# homeboard28.net
KiCad netlist of a schematic drawn in EAGLE
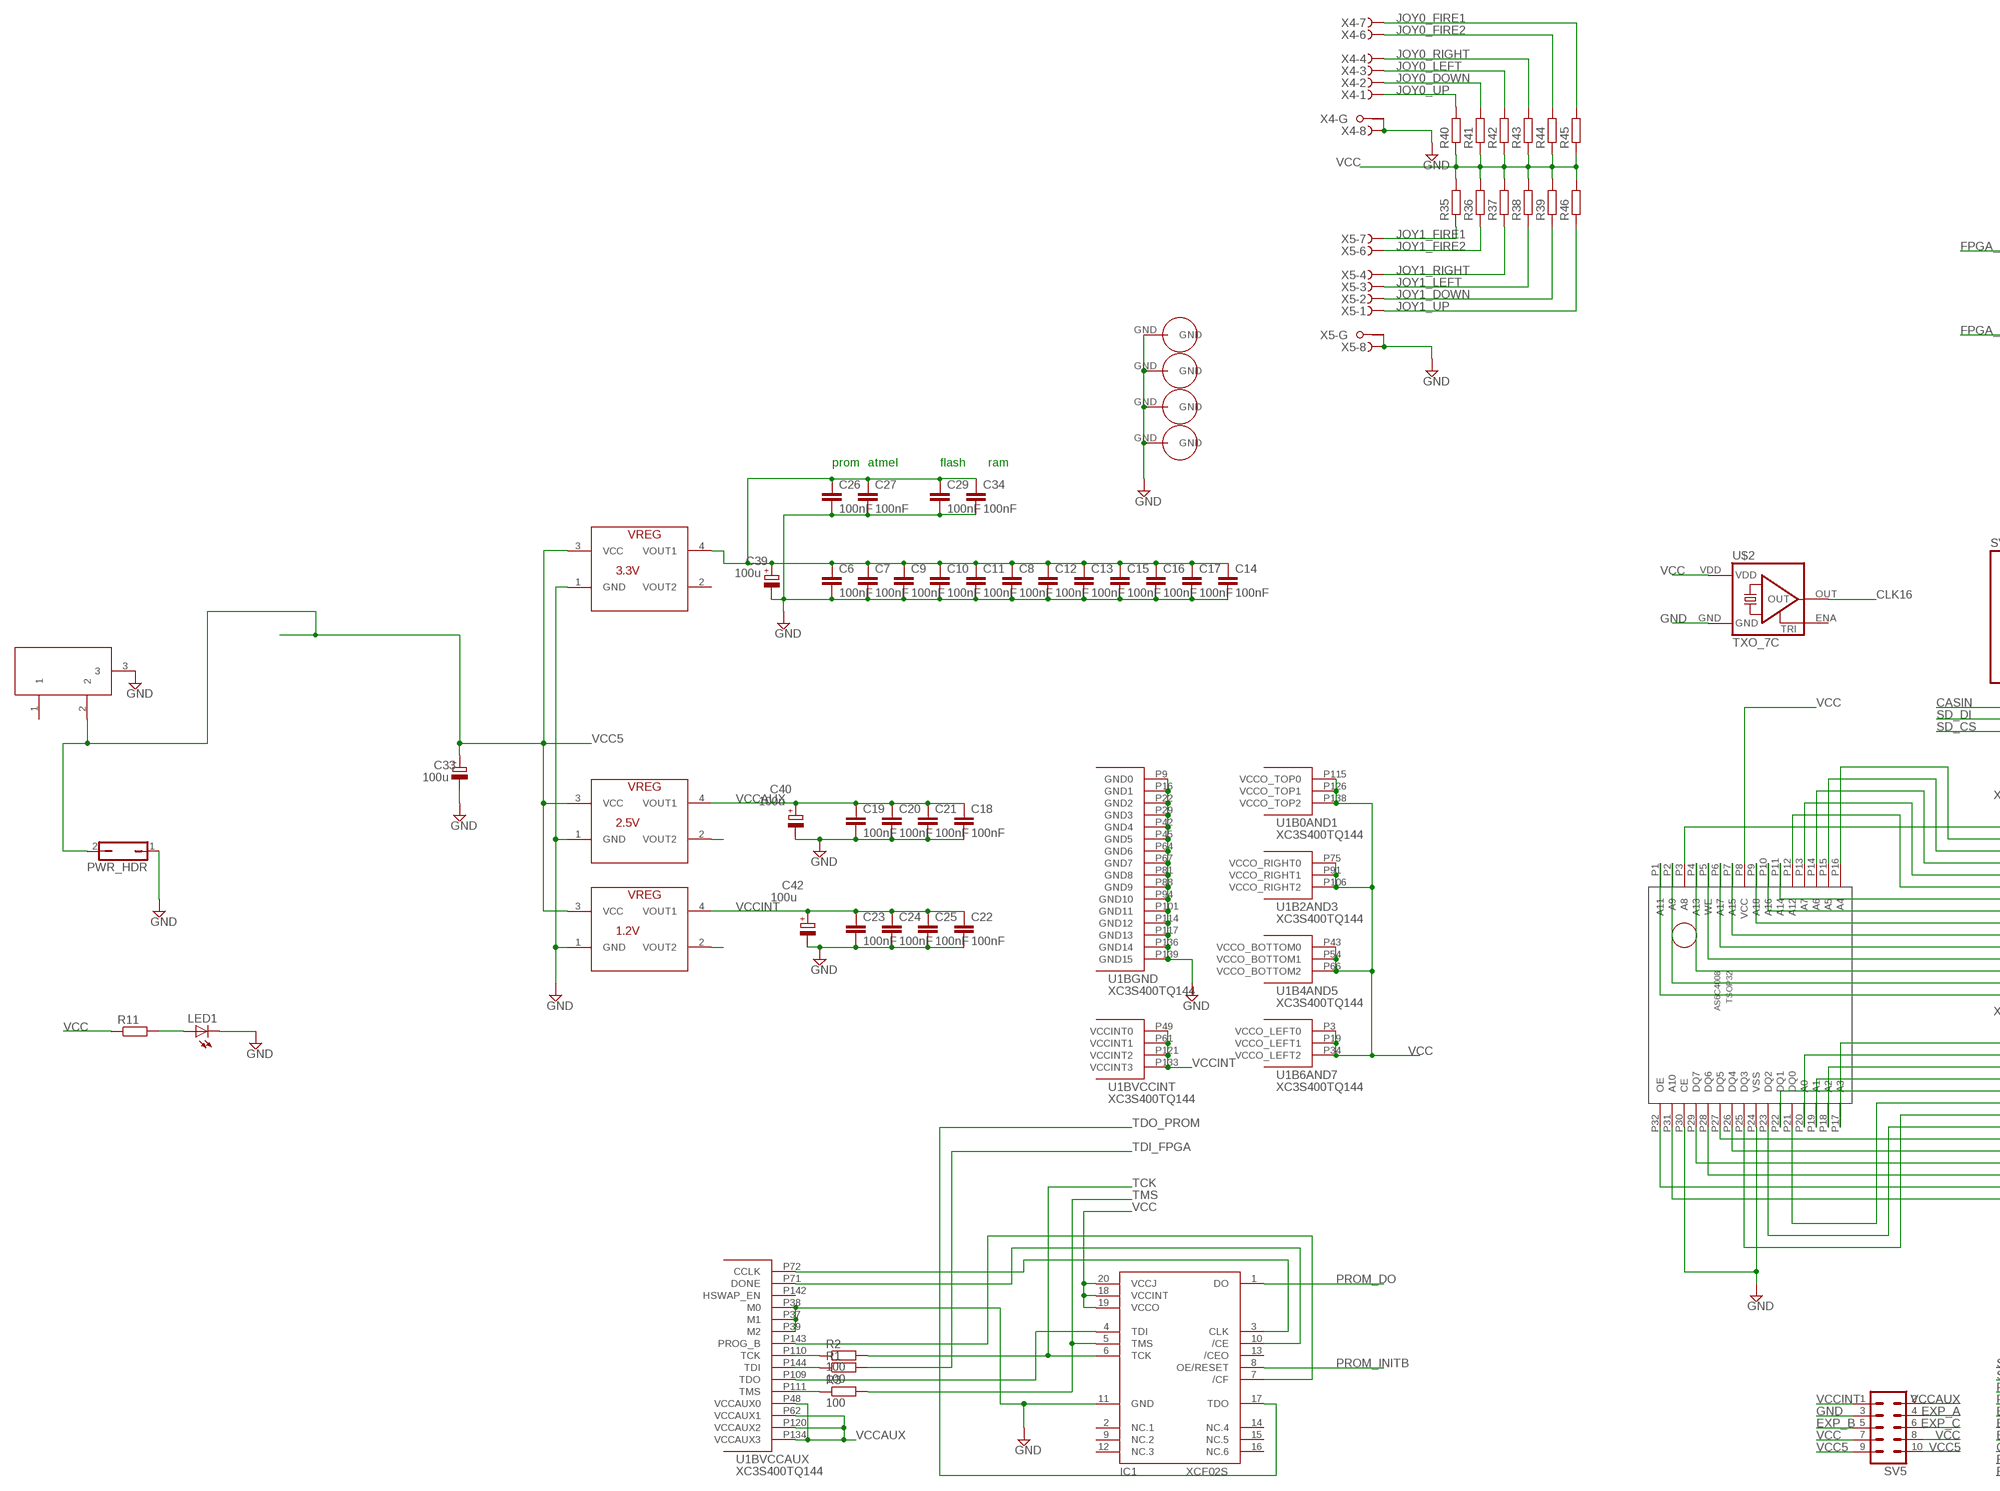
[diagram p0: schematic, sheet 1, part 1 of 3]
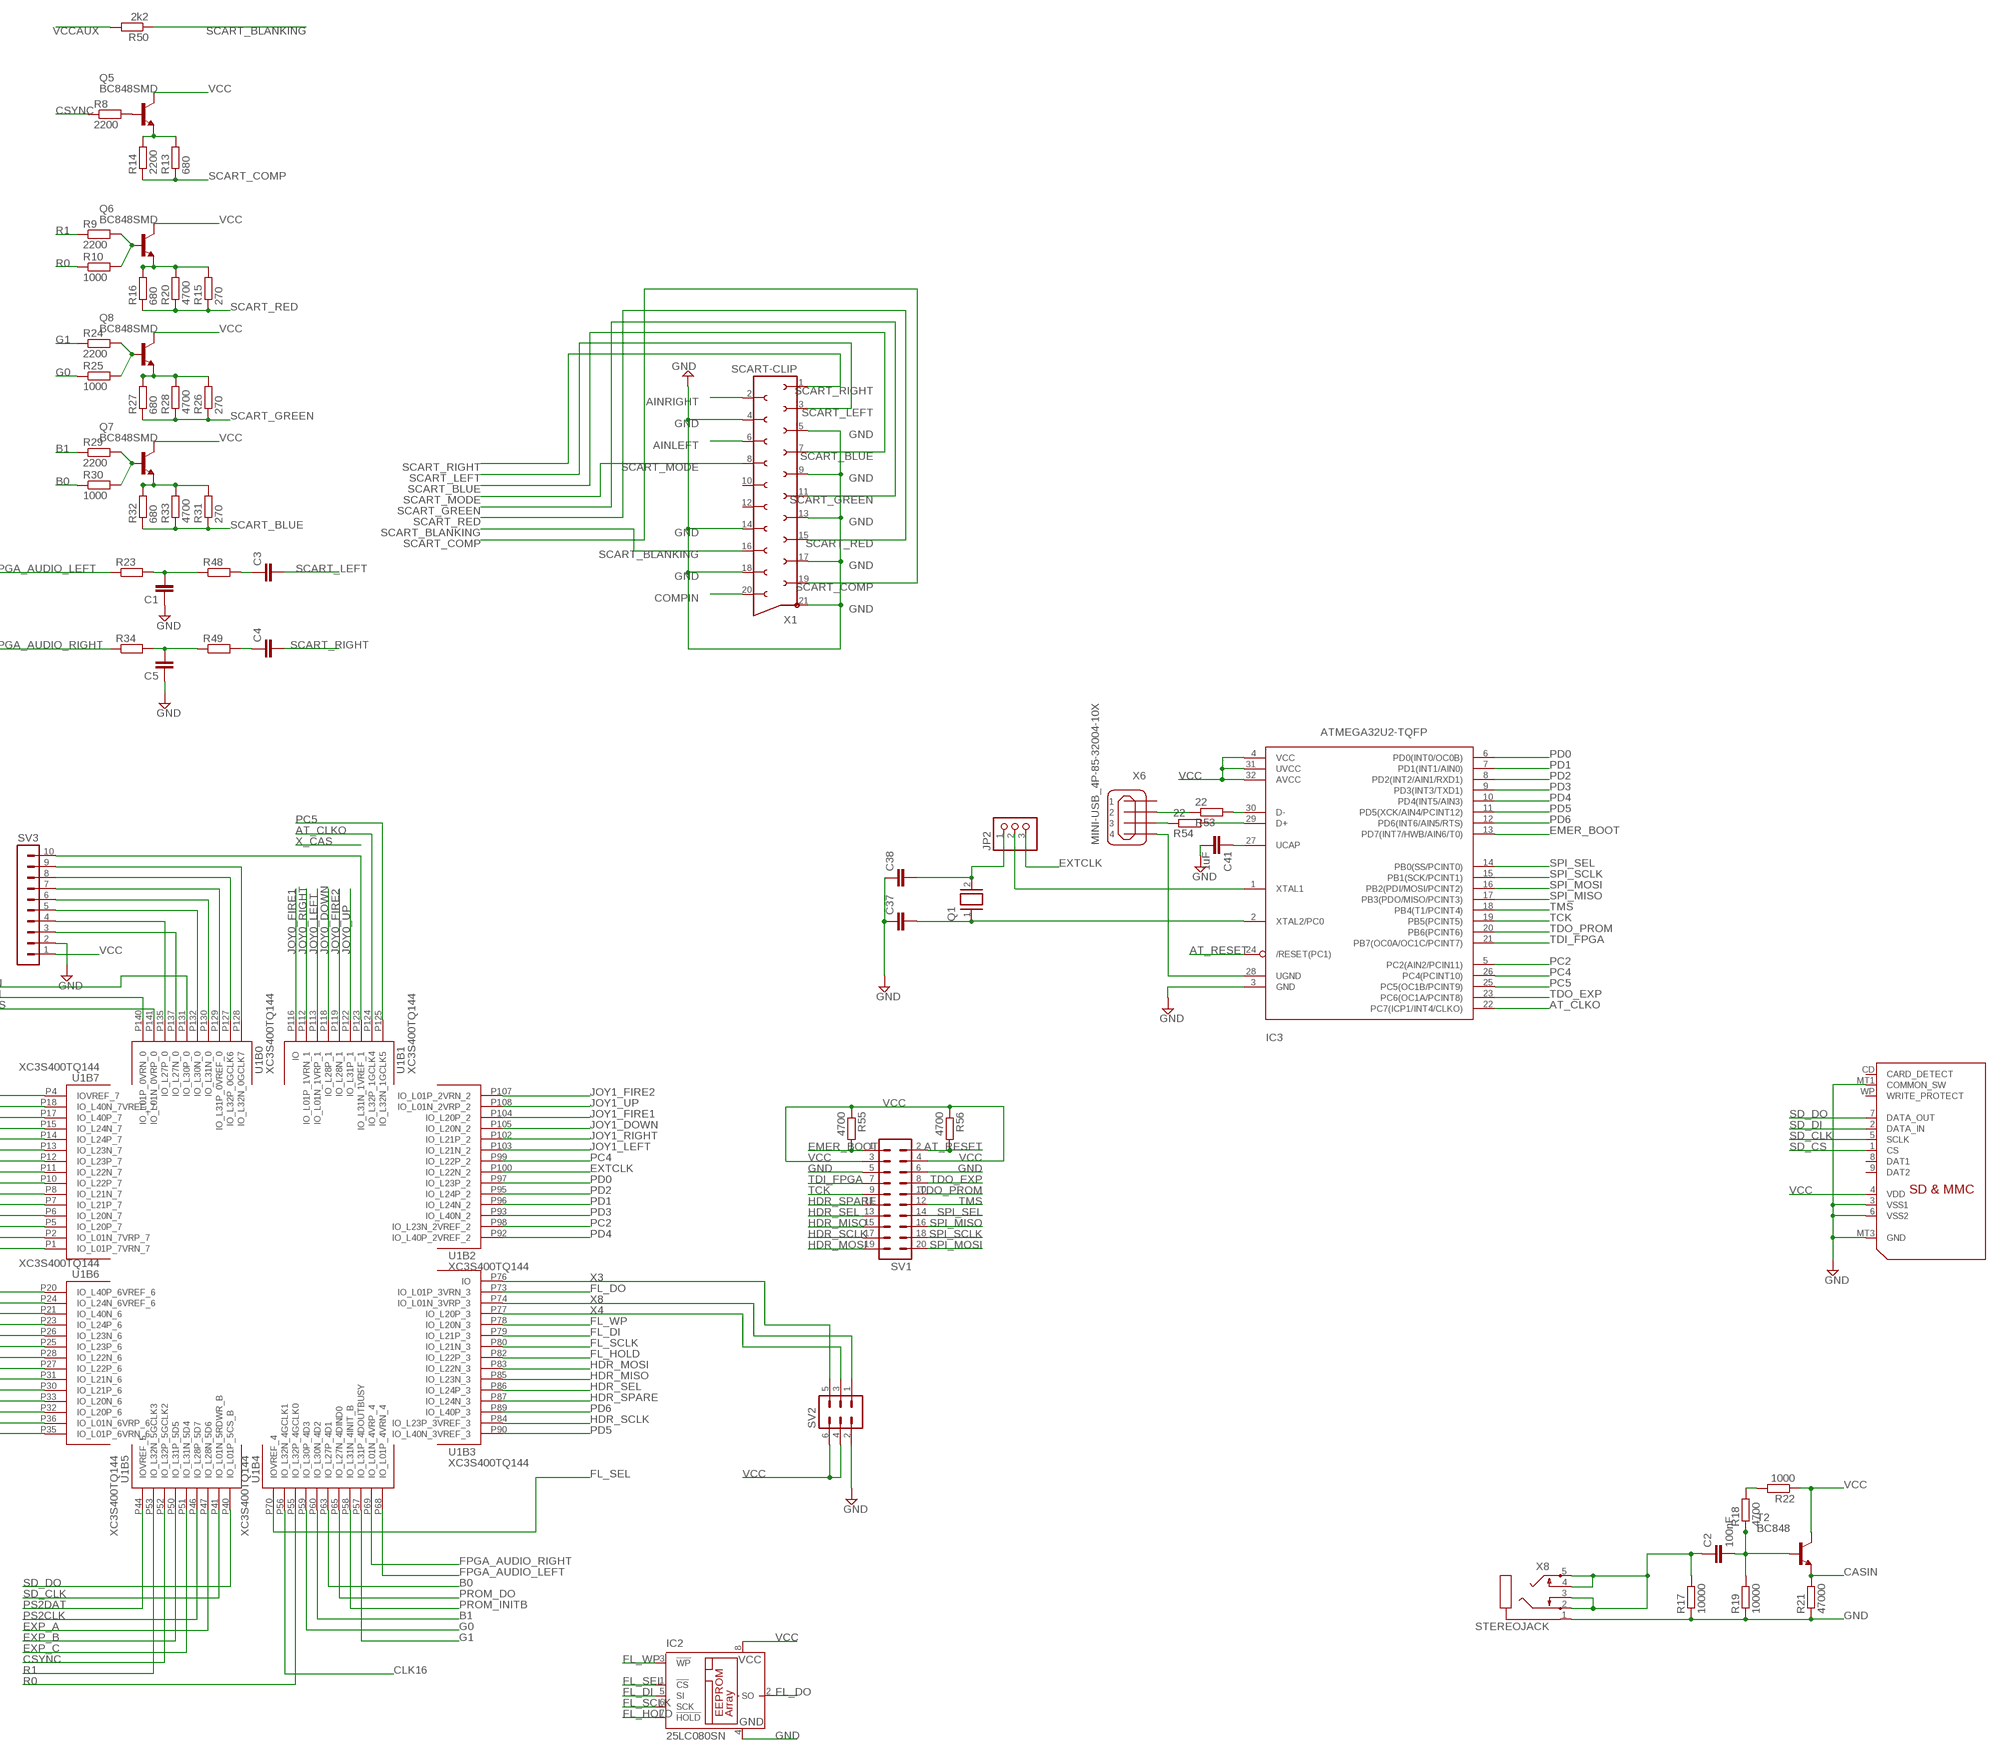
[diagram p1: schematic, sheet 1, part 2 of 3]
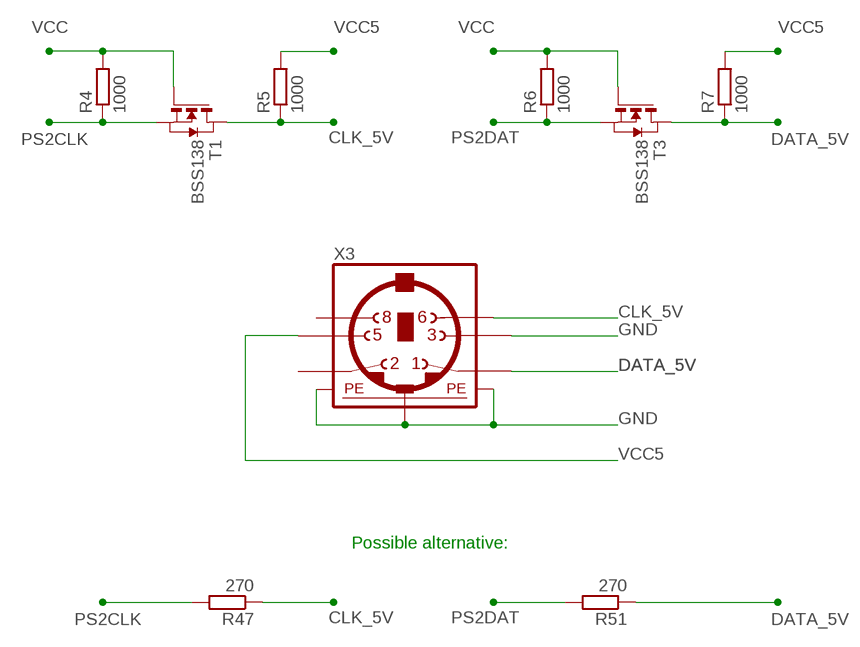
[diagram p2: schematic, sheet 1, part 3 of 3]

(export (version "E")
  (design (tool "Eeschema 10.0.6"))
  (components
    (comp (ref "C1")
      (value "C-EUC0603")
      (footprint "eagle-import:C0603")
      (libsource (lib "eagle-import") (part "resistor_C-EUC0603"))
    )
    (comp (ref "C2")
      (value "100nF")
      (footprint "eagle-import:C0603")
      (libsource (lib "eagle-import") (part "resistor_C-EUC0603"))
    )
    (comp (ref "C3")
      (value "C-EUC0603")
      (footprint "eagle-import:C0603")
      (libsource (lib "eagle-import") (part "resistor_C-EUC0603"))
    )
    (comp (ref "C4")
      (value "C-EUC0603")
      (footprint "eagle-import:C0603")
      (libsource (lib "eagle-import") (part "resistor_C-EUC0603"))
    )
    (comp (ref "C5")
      (value "C-EUC0603")
      (footprint "eagle-import:C0603")
      (libsource (lib "eagle-import") (part "resistor_C-EUC0603"))
    )
    (comp (ref "C6")
      (value "100nF")
      (footprint "eagle-import:C0603")
      (libsource (lib "eagle-import") (part "C-EUC0603"))
    )
    (comp (ref "C7")
      (value "100nF")
      (footprint "eagle-import:C0603")
      (libsource (lib "eagle-import") (part "C-EUC0603"))
    )
    (comp (ref "C8")
      (value "100nF")
      (footprint "eagle-import:C0603")
      (libsource (lib "eagle-import") (part "C-EUC0603"))
    )
    (comp (ref "C9")
      (value "100nF")
      (footprint "eagle-import:C0603")
      (libsource (lib "eagle-import") (part "C-EUC0603"))
    )
    (comp (ref "C10")
      (value "100nF")
      (footprint "eagle-import:C0603")
      (libsource (lib "eagle-import") (part "C-EUC0603"))
    )
    (comp (ref "C11")
      (value "100nF")
      (footprint "eagle-import:C0603")
      (libsource (lib "eagle-import") (part "C-EUC0603"))
    )
    (comp (ref "C12")
      (value "100nF")
      (footprint "eagle-import:C0603")
      (libsource (lib "eagle-import") (part "C-EUC0603"))
    )
    (comp (ref "C13")
      (value "100nF")
      (footprint "eagle-import:C0603")
      (libsource (lib "eagle-import") (part "C-EUC0603"))
    )
    (comp (ref "C14")
      (value "100nF")
      (footprint "eagle-import:C0603")
      (libsource (lib "eagle-import") (part "C-EUC0603"))
    )
    (comp (ref "C15")
      (value "100nF")
      (footprint "eagle-import:C0603")
      (libsource (lib "eagle-import") (part "C-EUC0603"))
    )
    (comp (ref "C16")
      (value "100nF")
      (footprint "eagle-import:C0603")
      (libsource (lib "eagle-import") (part "C-EUC0603"))
    )
    (comp (ref "C17")
      (value "100nF")
      (footprint "eagle-import:C0603")
      (libsource (lib "eagle-import") (part "C-EUC0603"))
    )
    (comp (ref "C18")
      (value "100nF")
      (footprint "eagle-import:C0603")
      (libsource (lib "eagle-import") (part "C-EUC0603"))
    )
    (comp (ref "C19")
      (value "100nF")
      (footprint "eagle-import:C0603")
      (libsource (lib "eagle-import") (part "C-EUC0603"))
    )
    (comp (ref "C20")
      (value "100nF")
      (footprint "eagle-import:C0603")
      (libsource (lib "eagle-import") (part "C-EUC0603"))
    )
    (comp (ref "C21")
      (value "100nF")
      (footprint "eagle-import:C0603")
      (libsource (lib "eagle-import") (part "C-EUC0603"))
    )
    (comp (ref "C22")
      (value "100nF")
      (footprint "eagle-import:C0603")
      (libsource (lib "eagle-import") (part "C-EUC0603"))
    )
    (comp (ref "C23")
      (value "100nF")
      (footprint "eagle-import:C0603")
      (libsource (lib "eagle-import") (part "C-EUC0603"))
    )
    (comp (ref "C24")
      (value "100nF")
      (footprint "eagle-import:C0603")
      (libsource (lib "eagle-import") (part "C-EUC0603"))
    )
    (comp (ref "C25")
      (value "100nF")
      (footprint "eagle-import:C0603")
      (libsource (lib "eagle-import") (part "C-EUC0603"))
    )
    (comp (ref "C26")
      (value "100nF")
      (footprint "eagle-import:C0603")
      (libsource (lib "eagle-import") (part "C-EUC0603"))
    )
    (comp (ref "C27")
      (value "100nF")
      (footprint "eagle-import:C0603")
      (libsource (lib "eagle-import") (part "C-EUC0603"))
    )
    (comp (ref "C29")
      (value "100nF")
      (footprint "eagle-import:C0603")
      (libsource (lib "eagle-import") (part "C-EUC0603"))
    )
    (comp (ref "C33")
      (value "100u")
      (footprint "eagle-import:PANASONIC_D")
      (libsource (lib "eagle-import") (part "CPOL-EUD"))
    )
    (comp (ref "C34")
      (value "100nF")
      (footprint "eagle-import:C0603")
      (libsource (lib "eagle-import") (part "C-EUC0603"))
    )
    (comp (ref "C37")
      (value "C-EUC0805")
      (footprint "eagle-import:C0805")
      (libsource (lib "eagle-import") (part "C-EUC0805"))
    )
    (comp (ref "C38")
      (value "C-EUC0805")
      (footprint "eagle-import:C0805")
      (libsource (lib "eagle-import") (part "C-EUC0805"))
    )
    (comp (ref "C39")
      (value "100u")
      (footprint "eagle-import:PANASONIC_D")
      (libsource (lib "eagle-import") (part "CPOL-EUD"))
    )
    (comp (ref "C40")
      (value "100u")
      (footprint "eagle-import:PANASONIC_D")
      (libsource (lib "eagle-import") (part "CPOL-EUD"))
    )
    (comp (ref "C41")
      (value "1uF")
      (footprint "eagle-import:C0805")
      (libsource (lib "eagle-import") (part "C-EUC0805"))
    )
    (comp (ref "C42")
      (value "100u")
      (footprint "eagle-import:PANASONIC_D")
      (libsource (lib "eagle-import") (part "CPOL-EUD"))
    )
    (comp (ref "IC1")
      (value "XCF02S")
      (footprint "eagle-import:VO20")
      (libsource (lib "eagle-import") (part "XCF02S"))
    )
    (comp (ref "IC2")
      (value "25LC080SN")
      (footprint "eagle-import:SO-08")
      (fields (field (name "MF") "MICROCHIP") (field (name "MPN") "25LC080/SN"))
      (libsource (lib "eagle-import") (part "25SNLC080"))
    )
    (comp (ref "IC3")
      (value "ATMEGA32U2-TQFP")
      (footprint "eagle-import:TQFP32-08")
      (libsource (lib "eagle-import") (part "ATMEGA32U2-TQFP"))
    )
    (comp (ref "JP2")
      (value "PINHD-1X3")
      (footprint "eagle-import:1X03")
      (libsource (lib "eagle-import") (part "PINHD-1X3"))
    )
    (comp (ref "LED1")
      (value "LEDCHIPLED_0805")
      (footprint "eagle-import:CHIPLED_0805")
      (libsource (lib "eagle-import") (part "LEDCHIPLED_0805"))
    )
    (comp (ref "PWR_HDR")
      (value "JP1Q")
      (footprint "eagle-import:JP1")
      (libsource (lib "eagle-import") (part "JP1Q"))
    )
    (comp (ref "Q1")
      (value "XTAL/S")
      (footprint "eagle-import:QS")
      (libsource (lib "eagle-import") (part "XTAL/S"))
    )
    (comp (ref "Q5")
      (value "BC848SMD")
      (footprint "eagle-import:SOT23")
      (libsource (lib "eagle-import") (part "BC848SMD"))
    )
    (comp (ref "Q6")
      (value "BC848SMD")
      (footprint "eagle-import:SOT23")
      (libsource (lib "eagle-import") (part "BC848SMD"))
    )
    (comp (ref "Q7")
      (value "BC848SMD")
      (footprint "eagle-import:SOT23")
      (libsource (lib "eagle-import") (part "BC848SMD"))
    )
    (comp (ref "Q8")
      (value "BC848SMD")
      (footprint "eagle-import:SOT23")
      (libsource (lib "eagle-import") (part "BC848SMD"))
    )
    (comp (ref "R1")
      (value "100")
      (footprint "eagle-import:R0805")
      (libsource (lib "eagle-import") (part "R-EU_R0805"))
    )
    (comp (ref "R2")
      (value "100")
      (footprint "eagle-import:R0805")
      (libsource (lib "eagle-import") (part "R-EU_R0805"))
    )
    (comp (ref "R3")
      (value "100")
      (footprint "eagle-import:R0805")
      (libsource (lib "eagle-import") (part "R-EU_R0805"))
    )
    (comp (ref "R4")
      (value "1000")
      (footprint "eagle-import:R0805")
      (libsource (lib "eagle-import") (part "R-EU_R0805"))
    )
    (comp (ref "R5")
      (value "1000")
      (footprint "eagle-import:R0805")
      (libsource (lib "eagle-import") (part "R-EU_R0805"))
    )
    (comp (ref "R6")
      (value "1000")
      (footprint "eagle-import:R0805")
      (libsource (lib "eagle-import") (part "R-EU_R0805"))
    )
    (comp (ref "R7")
      (value "1000")
      (footprint "eagle-import:R0805")
      (libsource (lib "eagle-import") (part "R-EU_R0805"))
    )
    (comp (ref "R8")
      (value "2200")
      (footprint "eagle-import:R0805")
      (libsource (lib "eagle-import") (part "R-EU_R0805"))
    )
    (comp (ref "R9")
      (value "2200")
      (footprint "eagle-import:R0805")
      (libsource (lib "eagle-import") (part "R-EU_R0805"))
    )
    (comp (ref "R10")
      (value "1000")
      (footprint "eagle-import:R0805")
      (libsource (lib "eagle-import") (part "R-EU_R0805"))
    )
    (comp (ref "R11")
      (value "R-EU_M0805")
      (footprint "eagle-import:M0805")
      (libsource (lib "eagle-import") (part "resistor_R-EU_M0805"))
    )
    (comp (ref "R13")
      (value "680")
      (footprint "eagle-import:R0805")
      (libsource (lib "eagle-import") (part "R-EU_R0805"))
    )
    (comp (ref "R14")
      (value "2200")
      (footprint "eagle-import:R0805")
      (libsource (lib "eagle-import") (part "R-EU_R0805"))
    )
    (comp (ref "R15")
      (value "270")
      (footprint "eagle-import:R0805")
      (libsource (lib "eagle-import") (part "R-EU_R0805"))
    )
    (comp (ref "R16")
      (value "680")
      (footprint "eagle-import:R0805")
      (libsource (lib "eagle-import") (part "R-EU_R0805"))
    )
    (comp (ref "R17")
      (value "10000")
      (footprint "eagle-import:R0805")
      (libsource (lib "eagle-import") (part "R-EU_R0805"))
    )
    (comp (ref "R18")
      (value "4700")
      (footprint "eagle-import:R0805")
      (libsource (lib "eagle-import") (part "R-EU_R0805"))
    )
    (comp (ref "R19")
      (value "10000")
      (footprint "eagle-import:R0805")
      (libsource (lib "eagle-import") (part "R-EU_R0805"))
    )
    (comp (ref "R20")
      (value "4700")
      (footprint "eagle-import:R0805")
      (libsource (lib "eagle-import") (part "R-EU_R0805"))
    )
    (comp (ref "R21")
      (value "47000")
      (footprint "eagle-import:R0805")
      (libsource (lib "eagle-import") (part "R-EU_R0805"))
    )
    (comp (ref "R22")
      (value "1000")
      (footprint "eagle-import:R0805")
      (libsource (lib "eagle-import") (part "R-EU_R0805"))
    )
    (comp (ref "R23")
      (value "R-EU_M0805")
      (footprint "eagle-import:M0805")
      (libsource (lib "eagle-import") (part "resistor_R-EU_M0805"))
    )
    (comp (ref "R24")
      (value "2200")
      (footprint "eagle-import:R0805")
      (libsource (lib "eagle-import") (part "R-EU_R0805"))
    )
    (comp (ref "R25")
      (value "1000")
      (footprint "eagle-import:R0805")
      (libsource (lib "eagle-import") (part "R-EU_R0805"))
    )
    (comp (ref "R26")
      (value "270")
      (footprint "eagle-import:R0805")
      (libsource (lib "eagle-import") (part "R-EU_R0805"))
    )
    (comp (ref "R27")
      (value "680")
      (footprint "eagle-import:R0805")
      (libsource (lib "eagle-import") (part "R-EU_R0805"))
    )
    (comp (ref "R28")
      (value "4700")
      (footprint "eagle-import:R0805")
      (libsource (lib "eagle-import") (part "R-EU_R0805"))
    )
    (comp (ref "R29")
      (value "2200")
      (footprint "eagle-import:R0805")
      (libsource (lib "eagle-import") (part "R-EU_R0805"))
    )
    (comp (ref "R30")
      (value "1000")
      (footprint "eagle-import:R0805")
      (libsource (lib "eagle-import") (part "R-EU_R0805"))
    )
    (comp (ref "R31")
      (value "270")
      (footprint "eagle-import:R0805")
      (libsource (lib "eagle-import") (part "R-EU_R0805"))
    )
    (comp (ref "R32")
      (value "680")
      (footprint "eagle-import:R0805")
      (libsource (lib "eagle-import") (part "R-EU_R0805"))
    )
    (comp (ref "R33")
      (value "4700")
      (footprint "eagle-import:R0805")
      (libsource (lib "eagle-import") (part "R-EU_R0805"))
    )
    (comp (ref "R34")
      (value "R-EU_M0805")
      (footprint "eagle-import:M0805")
      (libsource (lib "eagle-import") (part "resistor_R-EU_M0805"))
    )
    (comp (ref "R35")
      (value "R-EU_M0805")
      (footprint "eagle-import:M0805")
      (libsource (lib "eagle-import") (part "resistor_R-EU_M0805"))
    )
    (comp (ref "R36")
      (value "R-EU_M0805")
      (footprint "eagle-import:M0805")
      (libsource (lib "eagle-import") (part "resistor_R-EU_M0805"))
    )
    (comp (ref "R37")
      (value "R-EU_M0805")
      (footprint "eagle-import:M0805")
      (libsource (lib "eagle-import") (part "resistor_R-EU_M0805"))
    )
    (comp (ref "R38")
      (value "R-EU_M0805")
      (footprint "eagle-import:M0805")
      (libsource (lib "eagle-import") (part "resistor_R-EU_M0805"))
    )
    (comp (ref "R39")
      (value "R-EU_M0805")
      (footprint "eagle-import:M0805")
      (libsource (lib "eagle-import") (part "resistor_R-EU_M0805"))
    )
    (comp (ref "R40")
      (value "R-EU_M0805")
      (footprint "eagle-import:M0805")
      (libsource (lib "eagle-import") (part "resistor_R-EU_M0805"))
    )
    (comp (ref "R41")
      (value "R-EU_M0805")
      (footprint "eagle-import:M0805")
      (libsource (lib "eagle-import") (part "resistor_R-EU_M0805"))
    )
    (comp (ref "R42")
      (value "R-EU_M0805")
      (footprint "eagle-import:M0805")
      (libsource (lib "eagle-import") (part "resistor_R-EU_M0805"))
    )
    (comp (ref "R43")
      (value "R-EU_M0805")
      (footprint "eagle-import:M0805")
      (libsource (lib "eagle-import") (part "resistor_R-EU_M0805"))
    )
    (comp (ref "R44")
      (value "R-EU_M0805")
      (footprint "eagle-import:M0805")
      (libsource (lib "eagle-import") (part "resistor_R-EU_M0805"))
    )
    (comp (ref "R45")
      (value "R-EU_M0805")
      (footprint "eagle-import:M0805")
      (libsource (lib "eagle-import") (part "resistor_R-EU_M0805"))
    )
    (comp (ref "R46")
      (value "R-EU_M0805")
      (footprint "eagle-import:M0805")
      (libsource (lib "eagle-import") (part "resistor_R-EU_M0805"))
    )
    (comp (ref "R47")
      (value "270")
      (footprint "eagle-import:R0805")
      (libsource (lib "eagle-import") (part "R-EU_R0805"))
    )
    (comp (ref "R48")
      (value "R-EU_M0805")
      (footprint "eagle-import:M0805")
      (libsource (lib "eagle-import") (part "resistor_R-EU_M0805"))
    )
    (comp (ref "R49")
      (value "R-EU_M0805")
      (footprint "eagle-import:M0805")
      (libsource (lib "eagle-import") (part "resistor_R-EU_M0805"))
    )
    (comp (ref "R50")
      (value "2k2")
      (footprint "eagle-import:M0805")
      (libsource (lib "eagle-import") (part "resistor_R-EU_M0805"))
    )
    (comp (ref "R51")
      (value "270")
      (footprint "eagle-import:R0805")
      (libsource (lib "eagle-import") (part "R-EU_R0805"))
    )
    (comp (ref "R53")
      (value "22")
      (footprint "eagle-import:R0805")
      (libsource (lib "eagle-import") (part "R-EU_R0805"))
    )
    (comp (ref "R54")
      (value "22")
      (footprint "eagle-import:R0805")
      (libsource (lib "eagle-import") (part "R-EU_R0805"))
    )
    (comp (ref "R55")
      (value "4700")
      (footprint "eagle-import:R0805")
      (libsource (lib "eagle-import") (part "R-EU_R0805"))
    )
    (comp (ref "R56")
      (value "4700")
      (footprint "eagle-import:R0805")
      (libsource (lib "eagle-import") (part "R-EU_R0805"))
    )
    (comp (ref "REG1.2")
      (value "1.2V")
      (footprint "eagle-import:SOT223")
      (libsource (lib "eagle-import") (part "NX1117"))
    )
    (comp (ref "REG2.5")
      (value "2.5V")
      (footprint "eagle-import:SOT223")
      (libsource (lib "eagle-import") (part "NX1117"))
    )
    (comp (ref "SV1")
      (value "MA10-2")
      (footprint "eagle-import:MA10-2")
      (fields (field (name "OC_FARNELL") "unknown") (field (name "OC_NEWARK") "unknown"))
      (libsource (lib "eagle-import") (part "MA10-2"))
    )
    (comp (ref "SV2")
      (value "MA03-2")
      (footprint "eagle-import:MA03-2")
      (libsource (lib "eagle-import") (part "MA03-2"))
    )
    (comp (ref "SV3")
      (value "MA10-1")
      (footprint "eagle-import:MA10-1")
      (libsource (lib "eagle-import") (part "MA10-1"))
    )
    (comp (ref "SV5")
      (value "MA05-2")
      (footprint "eagle-import:MA05-2")
      (libsource (lib "eagle-import") (part "MA05-2"))
    )
    (comp (ref "T1")
      (value "BSS138")
      (footprint "eagle-import:SOT-23")
      (libsource (lib "eagle-import") (part "NMOSSOT23"))
    )
    (comp (ref "T2")
      (value "BC848")
      (footprint "eagle-import:SOT23")
      (libsource (lib "eagle-import") (part "BC848"))
    )
    (comp (ref "T3")
      (value "BSS138")
      (footprint "eagle-import:SOT-23")
      (libsource (lib "eagle-import") (part "NMOSSOT23"))
    )
    (comp (ref "U$1")
      (value "GNDHOLE")
      (footprint "eagle-import:GNDHOLE")
      (libsource (lib "eagle-import") (part "GNDHOLE"))
    )
    (comp (ref "U$2")
      (value "TXO_7C")
      (footprint "eagle-import:OSC_7C")
      (libsource (lib "eagle-import") (part "TXO_7C"))
    )
    (comp (ref "U$3")
      (value "SDMMCNOHOLE")
      (footprint "eagle-import:SDCARD-NOHOLE")
      (libsource (lib "eagle-import") (part "SDMMCNOHOLE"))
    )
    (comp (ref "U$4")
      (value "3.3V")
      (footprint "eagle-import:SOT223")
      (libsource (lib "eagle-import") (part "NX1117"))
    )
    (comp (ref "U$6")
      (value "AS6C4008")
      (footprint "eagle-import:TSOP32")
      (libsource (lib "eagle-import") (part "AS6C4008"))
    )
    (comp (ref "U$7")
      (value "GNDHOLE")
      (footprint "eagle-import:GNDHOLE")
      (libsource (lib "eagle-import") (part "GNDHOLE"))
    )
    (comp (ref "U$8")
      (value "GNDHOLE")
      (footprint "eagle-import:GNDHOLE")
      (libsource (lib "eagle-import") (part "GNDHOLE"))
    )
    (comp (ref "U$9")
      (value "GNDHOLE")
      (footprint "eagle-import:GNDHOLE")
      (libsource (lib "eagle-import") (part "GNDHOLE"))
    )
    (comp (ref "U1")
      (value "XC3S400TQ144")
      (footprint "eagle-import:TQ144")
      (libsource (lib "eagle-import") (part "XC3S400TQ144"))
    )
    (comp (ref "X1")
      (value "SCART-CLIP")
      (footprint "eagle-import:SCART-CLIP")
      (libsource (lib "eagle-import") (part "SCART-CLIP"))
    )
    (comp (ref "X3")
      (value "MINI_DIN_6")
      (footprint "eagle-import:M_DIN6")
      (libsource (lib "eagle-import") (part "MINI_DIN_6"))
    )
    (comp (ref "X4")
      (value "F09HPS")
      (footprint "eagle-import:F09HP")
      (libsource (lib "eagle-import") (part "F09HPS"))
    )
    (comp (ref "X5")
      (value "F09HPS")
      (footprint "eagle-import:F09HP")
      (libsource (lib "eagle-import") (part "F09HPS"))
    )
    (comp (ref "X6")
      (value "MINI-USB_4P-85-32004-10X")
      (footprint "eagle-import:85-32004-10X")
      (libsource (lib "eagle-import") (part "MINI-USB_4P-85-32004-10X"))
    )
    (comp (ref "X7")
      (value "DC21MMX")
      (footprint "eagle-import:DC-21MM")
      (libsource (lib "eagle-import") (part "DC21MMX"))
    )
    (comp (ref "X8")
      (value "STEREOJACK")
      (footprint "eagle-import:20-0137")
      (libsource (lib "eagle-import") (part "STEREOJACK"))
    )
  )
  (nets
    (net (code "1") (name "/1") (class "Default")
      (node (ref "X7") (pin "1") (pinfunction "1_1") (pintype "power_in"))
    )
    (net (code "2") (name "/AINLEFT") (class "Default")
      (node (ref "X1") (pin "6") (pinfunction "6_6") (pintype "passive"))
    )
    (net (code "3") (name "/AINRIGHT") (class "Default")
      (node (ref "X1") (pin "2") (pinfunction "2_2") (pintype "passive"))
    )
    (net (code "4") (name "/AT_CLKO") (class "Default")
      (node (ref "IC3") (pin "22") (pinfunction "PC7(ICP1/INT4/CLKO)_22") (pintype "bidirectional"))
      (node (ref "U1") (pin "P124") (pinfunction "IO_L32P_1GCLK4_P124") (pintype "bidirectional"))
    )
    (net (code "5") (name "/AT_RESET") (class "Default")
      (node (ref "IC3") (pin "24") (pinfunction "/RESET(PC1)_24") (pintype "bidirectional"))
      (node (ref "R56") (pin "2") (pinfunction "2_2") (pintype "passive"))
      (node (ref "SV1") (pin "2") (pinfunction "2_2") (pintype "passive"))
    )
    (net (code "6") (name "/B0") (class "Default")
      (node (ref "R30") (pin "1") (pinfunction "1_1") (pintype "passive"))
      (node (ref "U1") (pin "P63") (pinfunction "IO_L27P_4D1_P63") (pintype "bidirectional"))
    )
    (net (code "7") (name "/B1") (class "Default")
      (node (ref "R29") (pin "1") (pinfunction "1_1") (pintype "passive"))
      (node (ref "U1") (pin "P60") (pinfunction "IO_L30N_4D2_P60") (pintype "bidirectional"))
    )
    (net (code "8") (name "/CASIN") (class "Default")
      (node (ref "R21") (pin "2") (pinfunction "2_2") (pintype "passive"))
      (node (ref "T2") (pin "2") (pinfunction "E_2") (pintype "passive"))
      (node (ref "U1") (pin "P131") (pinfunction "IO_L30P_0_P131") (pintype "bidirectional"))
    )
    (net (code "9") (name "/CLK16") (class "Default")
      (node (ref "U$2") (pin "OUT") (pinfunction "OUT_OUT") (pintype "output"))
      (node (ref "U1") (pin "P56") (pinfunction "IO_L32N_4GCLK1_P56") (pintype "bidirectional"))
    )
    (net (code "10") (name "/CLK_5V") (class "Default")
      (node (ref "R47") (pin "1") (pinfunction "1_1") (pintype "passive"))
      (node (ref "R5") (pin "1") (pinfunction "1_1") (pintype "passive"))
      (node (ref "T1") (pin "1") (pinfunction "D_1") (pintype "passive"))
      (node (ref "X3") (pin "6") (pinfunction "6_6") (pintype "passive"))
    )
    (net (code "11") (name "/COMPIN") (class "Default")
      (node (ref "X1") (pin "20") (pinfunction "20_20") (pintype "passive"))
    )
    (net (code "12") (name "/CSYNC") (class "Default")
      (node (ref "R8") (pin "1") (pinfunction "1_1") (pintype "passive"))
      (node (ref "U1") (pin "P52") (pinfunction "IO_L32P_5GCLK2_P52") (pintype "bidirectional"))
    )
    (net (code "13") (name "/DATA_5V") (class "Default")
      (node (ref "R51") (pin "1") (pinfunction "1_1") (pintype "passive"))
      (node (ref "R7") (pin "1") (pinfunction "1_1") (pintype "passive"))
      (node (ref "T3") (pin "1") (pinfunction "D_1") (pintype "passive"))
      (node (ref "X3") (pin "1") (pinfunction "1_1") (pintype "passive"))
    )
    (net (code "14") (name "/EMER_BOOT") (class "Default")
      (node (ref "IC3") (pin "13") (pinfunction "PD7(INT7/HWB/AIN6/T0)_13") (pintype "bidirectional"))
      (node (ref "R55") (pin "2") (pinfunction "2_2") (pintype "passive"))
      (node (ref "SV1") (pin "1") (pinfunction "1_1") (pintype "passive"))
    )
    (net (code "15") (name "/EXP_A") (class "Default")
      (node (ref "SV5") (pin "4") (pinfunction "4_4") (pintype "passive"))
      (node (ref "U1") (pin "P47") (pinfunction "IO_L28N_5D6_P47") (pintype "bidirectional"))
    )
    (net (code "16") (name "/EXP_B") (class "Default")
      (node (ref "SV5") (pin "5") (pinfunction "5_5") (pintype "passive"))
      (node (ref "U1") (pin "P50") (pinfunction "IO_L31P_5D5_P50") (pintype "bidirectional"))
    )
    (net (code "17") (name "/EXP_C") (class "Default")
      (node (ref "SV5") (pin "6") (pinfunction "6_6") (pintype "passive"))
      (node (ref "U1") (pin "P51") (pinfunction "IO_L31N_5D4_P51") (pintype "bidirectional"))
    )
    (net (code "18") (name "/EXTCLK") (class "Default")
      (node (ref "JP2") (pin "3") (pinfunction "3_3") (pintype "passive"))
      (node (ref "U1") (pin "P100") (pinfunction "IO_L22N_2_P100") (pintype "bidirectional"))
    )
    (net (code "19") (name "/FL_DI") (class "Default")
      (node (ref "IC2") (pin "5") (pinfunction "SI_5") (pintype "input"))
      (node (ref "U1") (pin "P79") (pinfunction "IO_L21P_3_P79") (pintype "bidirectional"))
    )
    (net (code "20") (name "/FL_DO") (class "Default")
      (node (ref "IC2") (pin "2") (pinfunction "SO_2") (pintype "bidirectional"))
      (node (ref "U1") (pin "P73") (pinfunction "IO_L01P_3VRN_3_P73") (pintype "bidirectional"))
    )
    (net (code "21") (name "/FL_HOLD") (class "Default")
      (node (ref "IC2") (pin "7") (pinfunction "~{HOLD}_7") (pintype "input"))
      (node (ref "U1") (pin "P82") (pinfunction "IO_L22P_3_P82") (pintype "bidirectional"))
    )
    (net (code "22") (name "/FL_SCLK") (class "Default")
      (node (ref "IC2") (pin "6") (pinfunction "SCK_6") (pintype "input"))
      (node (ref "U1") (pin "P80") (pinfunction "IO_L21N_3_P80") (pintype "bidirectional"))
    )
    (net (code "23") (name "/FL_SEL") (class "Default")
      (node (ref "IC2") (pin "1") (pinfunction "~{CS}_1") (pintype "input"))
      (node (ref "U1") (pin "P70") (pinfunction "IOVREF_4_P70") (pintype "bidirectional"))
    )
    (net (code "24") (name "/FL_WP") (class "Default")
      (node (ref "IC2") (pin "3") (pinfunction "~{WP}_3") (pintype "input"))
      (node (ref "U1") (pin "P78") (pinfunction "IO_L20N_3_P78") (pintype "bidirectional"))
    )
    (net (code "25") (name "/FPGA_AUDIO_LEFT") (class "Default")
      (node (ref "R23") (pin "1") (pinfunction "1_1") (pintype "passive"))
      (node (ref "U1") (pin "P68") (pinfunction "IO_L01P_4VRN_4_P68") (pintype "bidirectional"))
    )
    (net (code "26") (name "/FPGA_AUDIO_RIGHT") (class "Default")
      (node (ref "R34") (pin "1") (pinfunction "1_1") (pintype "passive"))
      (node (ref "U1") (pin "P69") (pinfunction "IO_L01N_4VRP_4_P69") (pintype "bidirectional"))
    )
    (net (code "27") (name "/G0") (class "Default")
      (node (ref "R25") (pin "1") (pinfunction "1_1") (pintype "passive"))
      (node (ref "U1") (pin "P59") (pinfunction "IO_L30P_4D3_P59") (pintype "bidirectional"))
    )
    (net (code "28") (name "/G1") (class "Default")
      (node (ref "R24") (pin "1") (pinfunction "1_1") (pintype "passive"))
      (node (ref "U1") (pin "P57") (pinfunction "IO_L31P_4DOUTBUSY_P57") (pintype "bidirectional"))
    )
    (net (code "29") (name "/HDR_MISO") (class "Default")
      (node (ref "SV1") (pin "15") (pinfunction "15_15") (pintype "passive"))
      (node (ref "U1") (pin "P85") (pinfunction "IO_L23N_3_P85") (pintype "bidirectional"))
    )
    (net (code "30") (name "/HDR_MOSI") (class "Default")
      (node (ref "SV1") (pin "19") (pinfunction "19_19") (pintype "passive"))
      (node (ref "U1") (pin "P83") (pinfunction "IO_L22N_3_P83") (pintype "bidirectional"))
    )
    (net (code "31") (name "/HDR_SCLK") (class "Default")
      (node (ref "SV1") (pin "17") (pinfunction "17_17") (pintype "passive"))
      (node (ref "U1") (pin "P84") (pinfunction "IO_L23P_3VREF_3_P84") (pintype "bidirectional"))
    )
    (net (code "32") (name "/HDR_SEL") (class "Default")
      (node (ref "SV1") (pin "13") (pinfunction "13_13") (pintype "passive"))
      (node (ref "U1") (pin "P86") (pinfunction "IO_L24P_3_P86") (pintype "bidirectional"))
    )
    (net (code "33") (name "/HDR_SPARE") (class "Default")
      (node (ref "SV1") (pin "11") (pinfunction "11_11") (pintype "passive"))
      (node (ref "U1") (pin "P87") (pinfunction "IO_L24N_3_P87") (pintype "bidirectional"))
    )
    (net (code "34") (name "/JOY0_DOWN") (class "Default")
      (node (ref "R41") (pin "2") (pinfunction "2_2") (pintype "passive"))
      (node (ref "U1") (pin "P118") (pinfunction "IO_L28P_1_P118") (pintype "bidirectional"))
      (node (ref "X4") (pin "2") (pinfunction "F_2") (pintype "passive"))
    )
    (net (code "35") (name "/JOY0_FIRE1") (class "Default")
      (node (ref "R45") (pin "2") (pinfunction "2_2") (pintype "passive"))
      (node (ref "U1") (pin "P116") (pinfunction "IO_P116") (pintype "bidirectional"))
      (node (ref "X4") (pin "7") (pinfunction "F_7") (pintype "passive"))
    )
    (net (code "36") (name "/JOY0_FIRE2") (class "Default")
      (node (ref "R44") (pin "2") (pinfunction "2_2") (pintype "passive"))
      (node (ref "U1") (pin "P119") (pinfunction "IO_L28N_1_P119") (pintype "bidirectional"))
      (node (ref "X4") (pin "6") (pinfunction "F_6") (pintype "passive"))
    )
    (net (code "37") (name "/JOY0_LEFT") (class "Default")
      (node (ref "R42") (pin "2") (pinfunction "2_2") (pintype "passive"))
      (node (ref "U1") (pin "P113") (pinfunction "IO_L01N_1VRP_1_P113") (pintype "bidirectional"))
      (node (ref "X4") (pin "3") (pinfunction "F_3") (pintype "passive"))
    )
    (net (code "38") (name "/JOY0_RIGHT") (class "Default")
      (node (ref "R43") (pin "2") (pinfunction "2_2") (pintype "passive"))
      (node (ref "U1") (pin "P112") (pinfunction "IO_L01P_1VRN_1_P112") (pintype "bidirectional"))
      (node (ref "X4") (pin "4") (pinfunction "F_4") (pintype "passive"))
    )
    (net (code "39") (name "/JOY0_UP") (class "Default")
      (node (ref "R40") (pin "2") (pinfunction "2_2") (pintype "passive"))
      (node (ref "U1") (pin "P122") (pinfunction "IO_L31P_1_P122") (pintype "bidirectional"))
      (node (ref "X4") (pin "1") (pinfunction "F_1") (pintype "passive"))
    )
    (net (code "40") (name "/JOY1_DOWN") (class "Default")
      (node (ref "R39") (pin "1") (pinfunction "1_1") (pintype "passive"))
      (node (ref "U1") (pin "P105") (pinfunction "IO_L20N_2_P105") (pintype "bidirectional"))
      (node (ref "X5") (pin "2") (pinfunction "F_2") (pintype "passive"))
    )
    (net (code "41") (name "/JOY1_FIRE1") (class "Default")
      (node (ref "R35") (pin "1") (pinfunction "1_1") (pintype "passive"))
      (node (ref "U1") (pin "P104") (pinfunction "IO_L20P_2_P104") (pintype "bidirectional"))
      (node (ref "X5") (pin "7") (pinfunction "F_7") (pintype "passive"))
    )
    (net (code "42") (name "/JOY1_FIRE2") (class "Default")
      (node (ref "R36") (pin "1") (pinfunction "1_1") (pintype "passive"))
      (node (ref "U1") (pin "P107") (pinfunction "IO_L01P_2VRN_2_P107") (pintype "bidirectional"))
      (node (ref "X5") (pin "6") (pinfunction "F_6") (pintype "passive"))
    )
    (net (code "43") (name "/JOY1_LEFT") (class "Default")
      (node (ref "R38") (pin "1") (pinfunction "1_1") (pintype "passive"))
      (node (ref "U1") (pin "P103") (pinfunction "IO_L21N_2_P103") (pintype "bidirectional"))
      (node (ref "X5") (pin "3") (pinfunction "F_3") (pintype "passive"))
    )
    (net (code "44") (name "/JOY1_RIGHT") (class "Default")
      (node (ref "R37") (pin "1") (pinfunction "1_1") (pintype "passive"))
      (node (ref "U1") (pin "P102") (pinfunction "IO_L21P_2_P102") (pintype "bidirectional"))
      (node (ref "X5") (pin "4") (pinfunction "F_4") (pintype "passive"))
    )
    (net (code "45") (name "/JOY1_UP") (class "Default")
      (node (ref "R46") (pin "1") (pinfunction "1_1") (pintype "passive"))
      (node (ref "U1") (pin "P108") (pinfunction "IO_L01N_2VRP_2_P108") (pintype "bidirectional"))
      (node (ref "X5") (pin "1") (pinfunction "F_1") (pintype "passive"))
    )
    (net (code "46") (name "/PC2") (class "Default")
      (node (ref "IC3") (pin "5") (pinfunction "PC2(AIN2/PCIN11)_5") (pintype "bidirectional"))
      (node (ref "U1") (pin "P98") (pinfunction "IO_L23N_2VREF_2_P98") (pintype "bidirectional"))
    )
    (net (code "47") (name "/PC4") (class "Default")
      (node (ref "IC3") (pin "26") (pinfunction "PC4(PCINT10)_26") (pintype "bidirectional"))
      (node (ref "U1") (pin "P99") (pinfunction "IO_L22P_2_P99") (pintype "bidirectional"))
    )
    (net (code "48") (name "/PC5") (class "Default")
      (node (ref "IC3") (pin "25") (pinfunction "PC5(OC1B/PCINT9)_25") (pintype "bidirectional"))
      (node (ref "U1") (pin "P125") (pinfunction "IO_L32N_1GCLK5_P125") (pintype "bidirectional"))
    )
    (net (code "49") (name "/PD0") (class "Default")
      (node (ref "IC3") (pin "6") (pinfunction "PD0(INT0/OC0B)_6") (pintype "bidirectional"))
      (node (ref "U1") (pin "P97") (pinfunction "IO_L23P_2_P97") (pintype "bidirectional"))
    )
    (net (code "50") (name "/PD1") (class "Default")
      (node (ref "IC3") (pin "7") (pinfunction "PD1(INT1/AIN0)_7") (pintype "bidirectional"))
      (node (ref "U1") (pin "P96") (pinfunction "IO_L24N_2_P96") (pintype "bidirectional"))
    )
    (net (code "51") (name "/PD2") (class "Default")
      (node (ref "IC3") (pin "8") (pinfunction "PD2(INT2/AIN1/RXD1)_8") (pintype "bidirectional"))
      (node (ref "U1") (pin "P95") (pinfunction "IO_L24P_2_P95") (pintype "bidirectional"))
    )
    (net (code "52") (name "/PD3") (class "Default")
      (node (ref "IC3") (pin "9") (pinfunction "PD3(INT3/TXD1)_9") (pintype "bidirectional"))
      (node (ref "U1") (pin "P93") (pinfunction "IO_L40N_2_P93") (pintype "bidirectional"))
    )
    (net (code "53") (name "/PD4") (class "Default")
      (node (ref "IC3") (pin "10") (pinfunction "PD4(INT5/AIN3)_10") (pintype "bidirectional"))
      (node (ref "U1") (pin "P92") (pinfunction "IO_L40P_2VREF_2_P92") (pintype "bidirectional"))
    )
    (net (code "54") (name "/PD5") (class "Default")
      (node (ref "IC3") (pin "11") (pinfunction "PD5(XCK/AIN4/PCINT12)_11") (pintype "bidirectional"))
      (node (ref "U1") (pin "P90") (pinfunction "IO_L40N_3VREF_3_P90") (pintype "bidirectional"))
    )
    (net (code "55") (name "/PD6") (class "Default")
      (node (ref "IC3") (pin "12") (pinfunction "PD6(INT6/AIN5/RTS)_12") (pintype "bidirectional"))
      (node (ref "U1") (pin "P89") (pinfunction "IO_L40P_3_P89") (pintype "bidirectional"))
    )
    (net (code "56") (name "/PROM_DO") (class "Default")
      (node (ref "IC1") (pin "1") (pinfunction "DO_1") (pintype "bidirectional"))
      (node (ref "U1") (pin "P65") (pinfunction "IO_L27N_4DIND0_P65") (pintype "bidirectional"))
    )
    (net (code "57") (name "/PROM_INITB") (class "Default")
      (node (ref "IC1") (pin "8") (pinfunction "OE/RESET_8") (pintype "bidirectional"))
      (node (ref "U1") (pin "P58") (pinfunction "IO_L31N_4INIT_B_P58") (pintype "bidirectional"))
    )
    (net (code "58") (name "/PS2CLK") (class "Default")
      (node (ref "R4") (pin "1") (pinfunction "1_1") (pintype "passive"))
      (node (ref "R47") (pin "2") (pinfunction "2_2") (pintype "passive"))
      (node (ref "T1") (pin "2") (pinfunction "S_2") (pintype "passive"))
      (node (ref "U1") (pin "P46") (pinfunction "IO_L28P_5D7_P46") (pintype "bidirectional"))
    )
    (net (code "59") (name "/PS2DAT") (class "Default")
      (node (ref "R51") (pin "2") (pinfunction "2_2") (pintype "passive"))
      (node (ref "R6") (pin "1") (pinfunction "1_1") (pintype "passive"))
      (node (ref "T3") (pin "2") (pinfunction "S_2") (pintype "passive"))
      (node (ref "U1") (pin "P44") (pinfunction "IOVREF_5_P44") (pintype "bidirectional"))
    )
    (net (code "60") (name "/R0") (class "Default")
      (node (ref "R10") (pin "1") (pinfunction "1_1") (pintype "passive"))
      (node (ref "U1") (pin "P55") (pinfunction "IO_L32P_4GCLK0_P55") (pintype "bidirectional"))
    )
    (net (code "61") (name "/R1") (class "Default")
      (node (ref "R9") (pin "1") (pinfunction "1_1") (pintype "passive"))
      (node (ref "U1") (pin "P53") (pinfunction "IO_L32N_5GCLK3_P53") (pintype "bidirectional"))
    )
    (net (code "62") (name "/SCART_BLANKING") (class "Default")
      (node (ref "R50") (pin "1") (pinfunction "1_1") (pintype "passive"))
      (node (ref "X1") (pin "16") (pinfunction "16_16") (pintype "passive"))
    )
    (net (code "63") (name "/SCART_BLUE") (class "Default")
      (node (ref "R31") (pin "1") (pinfunction "1_1") (pintype "passive"))
      (node (ref "R32") (pin "1") (pinfunction "1_1") (pintype "passive"))
      (node (ref "R33") (pin "1") (pinfunction "1_1") (pintype "passive"))
      (node (ref "X1") (pin "7") (pinfunction "7_7") (pintype "passive"))
    )
    (net (code "64") (name "/SCART_COMP") (class "Default")
      (node (ref "R13") (pin "1") (pinfunction "1_1") (pintype "passive"))
      (node (ref "R14") (pin "1") (pinfunction "1_1") (pintype "passive"))
      (node (ref "X1") (pin "19") (pinfunction "19_19") (pintype "passive"))
    )
    (net (code "65") (name "/SCART_GREEN") (class "Default")
      (node (ref "R26") (pin "1") (pinfunction "1_1") (pintype "passive"))
      (node (ref "R27") (pin "1") (pinfunction "1_1") (pintype "passive"))
      (node (ref "R28") (pin "1") (pinfunction "1_1") (pintype "passive"))
      (node (ref "X1") (pin "11") (pinfunction "11_11") (pintype "passive"))
    )
    (net (code "66") (name "/SCART_LEFT") (class "Default")
      (node (ref "C3") (pin "2") (pinfunction "2_2") (pintype "passive"))
      (node (ref "X1") (pin "3") (pinfunction "3_3") (pintype "passive"))
    )
    (net (code "67") (name "/SCART_MODE") (class "Default")
      (node (ref "X1") (pin "8") (pinfunction "8_8") (pintype "passive"))
    )
    (net (code "68") (name "/SCART_RED") (class "Default")
      (node (ref "R15") (pin "1") (pinfunction "1_1") (pintype "passive"))
      (node (ref "R16") (pin "1") (pinfunction "1_1") (pintype "passive"))
      (node (ref "R20") (pin "1") (pinfunction "1_1") (pintype "passive"))
      (node (ref "X1") (pin "15") (pinfunction "15_15") (pintype "passive"))
    )
    (net (code "69") (name "/SCART_RIGHT") (class "Default")
      (node (ref "C4") (pin "2") (pinfunction "2_2") (pintype "passive"))
      (node (ref "X1") (pin "1") (pinfunction "1_1") (pintype "passive"))
    )
    (net (code "70") (name "/SD_CLK") (class "Default")
      (node (ref "U$3") (pin "5") (pinfunction "SCLK_5") (pintype "input"))
      (node (ref "U1") (pin "P41") (pinfunction "IO_L01N_5RDWR_B_P41") (pintype "bidirectional"))
    )
    (net (code "71") (name "/SD_CS") (class "Default")
      (node (ref "U$3") (pin "1") (pinfunction "CS_1") (pintype "input"))
      (node (ref "U1") (pin "P141") (pinfunction "IO_L01N_0VRP_0_P141") (pintype "bidirectional"))
    )
    (net (code "72") (name "/SD_DI") (class "Default")
      (node (ref "U$3") (pin "2") (pinfunction "DATA_IN_2") (pintype "input"))
      (node (ref "U1") (pin "P140") (pinfunction "IO_L01P_0VRN_0_P140") (pintype "bidirectional"))
    )
    (net (code "73") (name "/SD_DO") (class "Default")
      (node (ref "U$3") (pin "7") (pinfunction "DATA_OUT_7") (pintype "output"))
      (node (ref "U1") (pin "P40") (pinfunction "IO_L01P_5CS_B_P40") (pintype "bidirectional"))
    )
    (net (code "74") (name "/SPI_MISO") (class "Default")
      (node (ref "IC3") (pin "17") (pinfunction "PB3(PDO/MISO/PCINT3)_17") (pintype "bidirectional"))
      (node (ref "SV1") (pin "16") (pinfunction "16_16") (pintype "passive"))
    )
    (net (code "75") (name "/SPI_MOSI") (class "Default")
      (node (ref "IC3") (pin "16") (pinfunction "PB2(PDI/MOSI/PCINT2)_16") (pintype "bidirectional"))
      (node (ref "SV1") (pin "20") (pinfunction "20_20") (pintype "passive"))
    )
    (net (code "76") (name "/SPI_SCLK") (class "Default")
      (node (ref "IC3") (pin "15") (pinfunction "PB1(SCK/PCINT1)_15") (pintype "bidirectional"))
      (node (ref "SV1") (pin "18") (pinfunction "18_18") (pintype "passive"))
    )
    (net (code "77") (name "/SPI_SEL") (class "Default")
      (node (ref "IC3") (pin "14") (pinfunction "PB0(SS/PCINT0)_14") (pintype "bidirectional"))
      (node (ref "SV1") (pin "14") (pinfunction "14_14") (pintype "passive"))
    )
    (net (code "78") (name "/TCK") (class "Default")
      (node (ref "IC1") (pin "6") (pinfunction "TCK_6") (pintype "bidirectional"))
      (node (ref "IC3") (pin "19") (pinfunction "PB5(PCINT5)_19") (pintype "bidirectional"))
      (node (ref "R2") (pin "2") (pinfunction "2_2") (pintype "passive"))
      (node (ref "SV1") (pin "9") (pinfunction "9_9") (pintype "passive"))
    )
    (net (code "79") (name "/TDI_FPGA") (class "Default")
      (node (ref "IC3") (pin "21") (pinfunction "PB7(OC0A/OC1C/PCINT7)_21") (pintype "bidirectional"))
      (node (ref "R1") (pin "2") (pinfunction "2_2") (pintype "passive"))
      (node (ref "SV1") (pin "7") (pinfunction "7_7") (pintype "passive"))
    )
    (net (code "80") (name "/TDO_EXP") (class "Default")
      (node (ref "IC3") (pin "23") (pinfunction "PC6(OC1A/PCINT8)_23") (pintype "bidirectional"))
      (node (ref "SV1") (pin "8") (pinfunction "8_8") (pintype "passive"))
    )
    (net (code "81") (name "/TDO_PROM") (class "Default")
      (node (ref "IC1") (pin "17") (pinfunction "TDO_17") (pintype "bidirectional"))
      (node (ref "IC3") (pin "20") (pinfunction "PB6(PCINT6)_20") (pintype "bidirectional"))
      (node (ref "SV1") (pin "10") (pinfunction "10_10") (pintype "passive"))
    )
    (net (code "82") (name "/TMS") (class "Default")
      (node (ref "IC1") (pin "5") (pinfunction "TMS_5") (pintype "bidirectional"))
      (node (ref "IC3") (pin "18") (pinfunction "PB4(T1/PCINT4)_18") (pintype "bidirectional"))
      (node (ref "R3") (pin "2") (pinfunction "2_2") (pintype "passive"))
      (node (ref "SV1") (pin "12") (pinfunction "12_12") (pintype "passive"))
    )
    (net (code "83") (name "/VCC") (class "Default")
      (node (ref "C10") (pin "1") (pinfunction "1_1") (pintype "passive"))
      (node (ref "C11") (pin "1") (pinfunction "1_1") (pintype "passive"))
      (node (ref "C12") (pin "1") (pinfunction "1_1") (pintype "passive"))
      (node (ref "C13") (pin "1") (pinfunction "1_1") (pintype "passive"))
      (node (ref "C14") (pin "1") (pinfunction "1_1") (pintype "passive"))
      (node (ref "C15") (pin "1") (pinfunction "1_1") (pintype "passive"))
      (node (ref "C16") (pin "1") (pinfunction "1_1") (pintype "passive"))
      (node (ref "C17") (pin "1") (pinfunction "1_1") (pintype "passive"))
      (node (ref "C26") (pin "1") (pinfunction "1_1") (pintype "passive"))
      (node (ref "C27") (pin "1") (pinfunction "1_1") (pintype "passive"))
      (node (ref "C29") (pin "1") (pinfunction "1_1") (pintype "passive"))
      (node (ref "C34") (pin "1") (pinfunction "1_1") (pintype "passive"))
      (node (ref "C39") (pin "+") (pinfunction "+_+") (pintype "passive"))
      (node (ref "C6") (pin "1") (pinfunction "1_1") (pintype "passive"))
      (node (ref "C7") (pin "1") (pinfunction "1_1") (pintype "passive"))
      (node (ref "C8") (pin "1") (pinfunction "1_1") (pintype "passive"))
      (node (ref "C9") (pin "1") (pinfunction "1_1") (pintype "passive"))
      (node (ref "IC1") (pin "18") (pinfunction "VCCINT_18") (pintype "bidirectional"))
      (node (ref "IC1") (pin "19") (pinfunction "VCCO_19") (pintype "bidirectional"))
      (node (ref "IC1") (pin "20") (pinfunction "VCCJ_20") (pintype "bidirectional"))
      (node (ref "IC2") (pin "8") (pinfunction "VCC_8") (pintype "power_in"))
      (node (ref "IC3") (pin "31") (pinfunction "UVCC_31") (pintype "bidirectional"))
      (node (ref "IC3") (pin "32") (pinfunction "AVCC_32") (pintype "bidirectional"))
      (node (ref "IC3") (pin "4") (pinfunction "VCC_4") (pintype "bidirectional"))
      (node (ref "Q5") (pin "3") (pinfunction "C_3") (pintype "passive"))
      (node (ref "Q6") (pin "3") (pinfunction "C_3") (pintype "passive"))
      (node (ref "Q7") (pin "3") (pinfunction "C_3") (pintype "passive"))
      (node (ref "Q8") (pin "3") (pinfunction "C_3") (pintype "passive"))
      (node (ref "R11") (pin "1") (pinfunction "1_1") (pintype "passive"))
      (node (ref "R22") (pin "1") (pinfunction "1_1") (pintype "passive"))
      (node (ref "R35") (pin "2") (pinfunction "2_2") (pintype "passive"))
      (node (ref "R36") (pin "2") (pinfunction "2_2") (pintype "passive"))
      (node (ref "R37") (pin "2") (pinfunction "2_2") (pintype "passive"))
      (node (ref "R38") (pin "2") (pinfunction "2_2") (pintype "passive"))
      (node (ref "R39") (pin "2") (pinfunction "2_2") (pintype "passive"))
      (node (ref "R4") (pin "2") (pinfunction "2_2") (pintype "passive"))
      (node (ref "R40") (pin "1") (pinfunction "1_1") (pintype "passive"))
      (node (ref "R41") (pin "1") (pinfunction "1_1") (pintype "passive"))
      (node (ref "R42") (pin "1") (pinfunction "1_1") (pintype "passive"))
      (node (ref "R43") (pin "1") (pinfunction "1_1") (pintype "passive"))
      (node (ref "R44") (pin "1") (pinfunction "1_1") (pintype "passive"))
      (node (ref "R45") (pin "1") (pinfunction "1_1") (pintype "passive"))
      (node (ref "R46") (pin "2") (pinfunction "2_2") (pintype "passive"))
      (node (ref "R55") (pin "1") (pinfunction "1_1") (pintype "passive"))
      (node (ref "R56") (pin "1") (pinfunction "1_1") (pintype "passive"))
      (node (ref "R6") (pin "2") (pinfunction "2_2") (pintype "passive"))
      (node (ref "SV1") (pin "3") (pinfunction "3_3") (pintype "passive"))
      (node (ref "SV1") (pin "4") (pinfunction "4_4") (pintype "passive"))
      (node (ref "SV2") (pin "4") (pinfunction "4_4") (pintype "passive"))
      (node (ref "SV2") (pin "6") (pinfunction "6_6") (pintype "passive"))
      (node (ref "SV3") (pin "1") (pinfunction "1_1") (pintype "passive"))
      (node (ref "SV5") (pin "7") (pinfunction "7_7") (pintype "passive"))
      (node (ref "SV5") (pin "8") (pinfunction "8_8") (pintype "passive"))
      (node (ref "T1") (pin "3") (pinfunction "G_3") (pintype "passive"))
      (node (ref "T2") (pin "3") (pinfunction "C_3") (pintype "passive"))
      (node (ref "T3") (pin "3") (pinfunction "G_3") (pintype "passive"))
      (node (ref "U$2") (pin "VDD") (pinfunction "VDD_VDD") (pintype "power_in"))
      (node (ref "U$3") (pin "4") (pinfunction "VDD_4") (pintype "power_in"))
      (node (ref "U$4") (pin "4") (pinfunction "VOUT1_4") (pintype "bidirectional"))
      (node (ref "U$6") (pin "P8") (pinfunction "VCC_P8") (pintype "bidirectional"))
      (node (ref "U1") (pin "P106") (pinfunction "VCCO_RIGHT2_P106") (pintype "passive"))
      (node (ref "U1") (pin "P115") (pinfunction "VCCO_TOP0_P115") (pintype "passive"))
      (node (ref "U1") (pin "P126") (pinfunction "VCCO_TOP1_P126") (pintype "passive"))
      (node (ref "U1") (pin "P138") (pinfunction "VCCO_TOP2_P138") (pintype "passive"))
      (node (ref "U1") (pin "P19") (pinfunction "VCCO_LEFT1_P19") (pintype "passive"))
      (node (ref "U1") (pin "P3") (pinfunction "VCCO_LEFT0_P3") (pintype "passive"))
      (node (ref "U1") (pin "P34") (pinfunction "VCCO_LEFT2_P34") (pintype "passive"))
      (node (ref "U1") (pin "P43") (pinfunction "VCCO_BOTTOM0_P43") (pintype "passive"))
      (node (ref "U1") (pin "P54") (pinfunction "VCCO_BOTTOM1_P54") (pintype "passive"))
      (node (ref "U1") (pin "P66") (pinfunction "VCCO_BOTTOM2_P66") (pintype "passive"))
      (node (ref "U1") (pin "P75") (pinfunction "VCCO_RIGHT0_P75") (pintype "passive"))
      (node (ref "U1") (pin "P91") (pinfunction "VCCO_RIGHT1_P91") (pintype "passive"))
    )
    (net (code "84") (name "/VCC5") (class "Default")
      (node (ref "C33") (pin "+") (pinfunction "+_+") (pintype "passive"))
      (node (ref "PWR_HDR") (pin "2") (pinfunction "2_2") (pintype "passive"))
      (node (ref "R5") (pin "2") (pinfunction "2_2") (pintype "passive"))
      (node (ref "R7") (pin "2") (pinfunction "2_2") (pintype "passive"))
      (node (ref "REG1.2") (pin "3") (pinfunction "VCC_3") (pintype "bidirectional"))
      (node (ref "REG2.5") (pin "3") (pinfunction "VCC_3") (pintype "bidirectional"))
      (node (ref "SV5") (pin "10") (pinfunction "10_10") (pintype "passive"))
      (node (ref "SV5") (pin "9") (pinfunction "9_9") (pintype "passive"))
      (node (ref "U$4") (pin "3") (pinfunction "VCC_3") (pintype "bidirectional"))
      (node (ref "X3") (pin "5") (pinfunction "5_5") (pintype "passive"))
      (node (ref "X7") (pin "2") (pinfunction "2_2") (pintype "power_in"))
    )
    (net (code "85") (name "/VCCAUX") (class "Default")
      (node (ref "C18") (pin "1") (pinfunction "1_1") (pintype "passive"))
      (node (ref "C19") (pin "1") (pinfunction "1_1") (pintype "passive"))
      (node (ref "C20") (pin "1") (pinfunction "1_1") (pintype "passive"))
      (node (ref "C21") (pin "1") (pinfunction "1_1") (pintype "passive"))
      (node (ref "C40") (pin "+") (pinfunction "+_+") (pintype "passive"))
      (node (ref "R50") (pin "2") (pinfunction "2_2") (pintype "passive"))
      (node (ref "REG2.5") (pin "4") (pinfunction "VOUT1_4") (pintype "bidirectional"))
      (node (ref "SV5") (pin "2") (pinfunction "2_2") (pintype "passive"))
      (node (ref "U1") (pin "P120") (pinfunction "VCCAUX2_P120") (pintype "passive"))
      (node (ref "U1") (pin "P134") (pinfunction "VCCAUX3_P134") (pintype "passive"))
      (node (ref "U1") (pin "P48") (pinfunction "VCCAUX0_P48") (pintype "passive"))
      (node (ref "U1") (pin "P62") (pinfunction "VCCAUX1_P62") (pintype "passive"))
    )
    (net (code "86") (name "/VCCINT") (class "Default")
      (node (ref "C22") (pin "1") (pinfunction "1_1") (pintype "passive"))
      (node (ref "C23") (pin "1") (pinfunction "1_1") (pintype "passive"))
      (node (ref "C24") (pin "1") (pinfunction "1_1") (pintype "passive"))
      (node (ref "C25") (pin "1") (pinfunction "1_1") (pintype "passive"))
      (node (ref "C42") (pin "+") (pinfunction "+_+") (pintype "passive"))
      (node (ref "REG1.2") (pin "4") (pinfunction "VOUT1_4") (pintype "bidirectional"))
      (node (ref "SV5") (pin "1") (pinfunction "1_1") (pintype "passive"))
      (node (ref "U1") (pin "P121") (pinfunction "VCCINT2_P121") (pintype "passive"))
      (node (ref "U1") (pin "P133") (pinfunction "VCCINT3_P133") (pintype "passive"))
      (node (ref "U1") (pin "P49") (pinfunction "VCCINT0_P49") (pintype "passive"))
      (node (ref "U1") (pin "P61") (pinfunction "VCCINT1_P61") (pintype "passive"))
    )
    (net (code "87") (name "/X3") (class "Default")
      (node (ref "SV2") (pin "5") (pinfunction "5_5") (pintype "passive"))
      (node (ref "U1") (pin "P76") (pinfunction "IO_P76") (pintype "bidirectional"))
    )
    (net (code "88") (name "/X4") (class "Default")
      (node (ref "SV2") (pin "3") (pinfunction "3_3") (pintype "passive"))
      (node (ref "U1") (pin "P77") (pinfunction "IO_L20P_3_P77") (pintype "bidirectional"))
    )
    (net (code "89") (name "/X8") (class "Default")
      (node (ref "SV2") (pin "1") (pinfunction "1_1") (pintype "passive"))
      (node (ref "U1") (pin "P74") (pinfunction "IO_L01N_3VRP_3_P74") (pintype "bidirectional"))
    )
    (net (code "91") (name "GND") (class "Default")
      (node (ref "C1") (pin "1") (pinfunction "1_1") (pintype "passive"))
      (node (ref "C10") (pin "2") (pinfunction "2_2") (pintype "passive"))
      (node (ref "C11") (pin "2") (pinfunction "2_2") (pintype "passive"))
      (node (ref "C12") (pin "2") (pinfunction "2_2") (pintype "passive"))
      (node (ref "C13") (pin "2") (pinfunction "2_2") (pintype "passive"))
      (node (ref "C14") (pin "2") (pinfunction "2_2") (pintype "passive"))
      (node (ref "C15") (pin "2") (pinfunction "2_2") (pintype "passive"))
      (node (ref "C16") (pin "2") (pinfunction "2_2") (pintype "passive"))
      (node (ref "C17") (pin "2") (pinfunction "2_2") (pintype "passive"))
      (node (ref "C18") (pin "2") (pinfunction "2_2") (pintype "passive"))
      (node (ref "C19") (pin "2") (pinfunction "2_2") (pintype "passive"))
      (node (ref "C20") (pin "2") (pinfunction "2_2") (pintype "passive"))
      (node (ref "C21") (pin "2") (pinfunction "2_2") (pintype "passive"))
      (node (ref "C22") (pin "2") (pinfunction "2_2") (pintype "passive"))
      (node (ref "C23") (pin "2") (pinfunction "2_2") (pintype "passive"))
      (node (ref "C24") (pin "2") (pinfunction "2_2") (pintype "passive"))
      (node (ref "C25") (pin "2") (pinfunction "2_2") (pintype "passive"))
      (node (ref "C26") (pin "2") (pinfunction "2_2") (pintype "passive"))
      (node (ref "C27") (pin "2") (pinfunction "2_2") (pintype "passive"))
      (node (ref "C29") (pin "2") (pinfunction "2_2") (pintype "passive"))
      (node (ref "C33") (pin "-") (pinfunction "-_-") (pintype "passive"))
      (node (ref "C34") (pin "2") (pinfunction "2_2") (pintype "passive"))
      (node (ref "C37") (pin "1") (pinfunction "1_1") (pintype "passive"))
      (node (ref "C38") (pin "1") (pinfunction "1_1") (pintype "passive"))
      (node (ref "C39") (pin "-") (pinfunction "-_-") (pintype "passive"))
      (node (ref "C40") (pin "-") (pinfunction "-_-") (pintype "passive"))
      (node (ref "C41") (pin "2") (pinfunction "2_2") (pintype "passive"))
      (node (ref "C42") (pin "-") (pinfunction "-_-") (pintype "passive"))
      (node (ref "C5") (pin "1") (pinfunction "1_1") (pintype "passive"))
      (node (ref "C6") (pin "2") (pinfunction "2_2") (pintype "passive"))
      (node (ref "C7") (pin "2") (pinfunction "2_2") (pintype "passive"))
      (node (ref "C8") (pin "2") (pinfunction "2_2") (pintype "passive"))
      (node (ref "C9") (pin "2") (pinfunction "2_2") (pintype "passive"))
      (node (ref "IC1") (pin "11") (pinfunction "GND_11") (pintype "bidirectional"))
      (node (ref "IC2") (pin "4") (pinfunction "GND_4") (pintype "power_in"))
      (node (ref "IC3") (pin "3") (pinfunction "GND_3") (pintype "bidirectional"))
      (node (ref "LED1") (pin "C") (pinfunction "C_C") (pintype "passive"))
      (node (ref "PWR_HDR") (pin "1") (pinfunction "1_1") (pintype "passive"))
      (node (ref "R17") (pin "1") (pinfunction "1_1") (pintype "passive"))
      (node (ref "R19") (pin "1") (pinfunction "1_1") (pintype "passive"))
      (node (ref "R21") (pin "1") (pinfunction "1_1") (pintype "passive"))
      (node (ref "REG1.2") (pin "1") (pinfunction "GND_1") (pintype "bidirectional"))
      (node (ref "REG2.5") (pin "1") (pinfunction "GND_1") (pintype "bidirectional"))
      (node (ref "SV1") (pin "5") (pinfunction "5_5") (pintype "passive"))
      (node (ref "SV1") (pin "6") (pinfunction "6_6") (pintype "passive"))
      (node (ref "SV2") (pin "2") (pinfunction "2_2") (pintype "passive"))
      (node (ref "SV3") (pin "2") (pinfunction "2_2") (pintype "passive"))
      (node (ref "SV5") (pin "3") (pinfunction "3_3") (pintype "passive"))
      (node (ref "U$1") (pin "GND") (pinfunction "GND_GND") (pintype "bidirectional"))
      (node (ref "U$2") (pin "GND") (pinfunction "GND_GND") (pintype "power_in"))
      (node (ref "U$3") (pin "3") (pinfunction "VSS1_3") (pintype "power_in"))
      (node (ref "U$3") (pin "6") (pinfunction "VSS2_6") (pintype "power_in"))
      (node (ref "U$3") (pin "MT1") (pinfunction "COMMON_SW_MT1") (pintype "passive"))
      (node (ref "U$3") (pin "MT3") (pinfunction "GND_MT3") (pintype "power_in"))
      (node (ref "U$4") (pin "1") (pinfunction "GND_1") (pintype "bidirectional"))
      (node (ref "U$6") (pin "P24") (pinfunction "VSS_P24") (pintype "bidirectional"))
      (node (ref "U$6") (pin "P30") (pinfunction "CE_P30") (pintype "bidirectional"))
      (node (ref "U$7") (pin "GND") (pinfunction "GND_GND") (pintype "bidirectional"))
      (node (ref "U$8") (pin "GND") (pinfunction "GND_GND") (pintype "bidirectional"))
      (node (ref "U$9") (pin "GND") (pinfunction "GND_GND") (pintype "bidirectional"))
      (node (ref "U1") (pin "P101") (pinfunction "GND11_P101") (pintype "passive"))
      (node (ref "U1") (pin "P114") (pinfunction "GND12_P114") (pintype "passive"))
      (node (ref "U1") (pin "P117") (pinfunction "GND13_P117") (pintype "passive"))
      (node (ref "U1") (pin "P136") (pinfunction "GND14_P136") (pintype "passive"))
      (node (ref "U1") (pin "P139") (pinfunction "GND15_P139") (pintype "passive"))
      (node (ref "U1") (pin "P16") (pinfunction "GND1_P16") (pintype "passive"))
      (node (ref "U1") (pin "P22") (pinfunction "GND2_P22") (pintype "passive"))
      (node (ref "U1") (pin "P29") (pinfunction "GND3_P29") (pintype "passive"))
      (node (ref "U1") (pin "P37") (pinfunction "M1_P37") (pintype "bidirectional"))
      (node (ref "U1") (pin "P38") (pinfunction "M0_P38") (pintype "bidirectional"))
      (node (ref "U1") (pin "P39") (pinfunction "M2_P39") (pintype "bidirectional"))
      (node (ref "U1") (pin "P42") (pinfunction "GND4_P42") (pintype "passive"))
      (node (ref "U1") (pin "P45") (pinfunction "GND5_P45") (pintype "passive"))
      (node (ref "U1") (pin "P64") (pinfunction "GND6_P64") (pintype "passive"))
      (node (ref "U1") (pin "P67") (pinfunction "GND7_P67") (pintype "passive"))
      (node (ref "U1") (pin "P81") (pinfunction "GND8_P81") (pintype "passive"))
      (node (ref "U1") (pin "P88") (pinfunction "GND9_P88") (pintype "passive"))
      (node (ref "U1") (pin "P9") (pinfunction "GND0_P9") (pintype "passive"))
      (node (ref "U1") (pin "P94") (pinfunction "GND10_P94") (pintype "passive"))
      (node (ref "X1") (pin "13") (pinfunction "13_13") (pintype "passive"))
      (node (ref "X1") (pin "14") (pinfunction "14_14") (pintype "passive"))
      (node (ref "X1") (pin "17") (pinfunction "17_17") (pintype "passive"))
      (node (ref "X1") (pin "18") (pinfunction "18_18") (pintype "passive"))
      (node (ref "X1") (pin "21") (pinfunction "21_21") (pintype "passive"))
      (node (ref "X1") (pin "4") (pinfunction "4_4") (pintype "passive"))
      (node (ref "X1") (pin "5") (pinfunction "5_5") (pintype "passive"))
      (node (ref "X1") (pin "9") (pinfunction "9_9") (pintype "passive"))
      (node (ref "X3") (pin "3") (pinfunction "3_3") (pintype "passive"))
      (node (ref "X3") (pin "SH1") (pinfunction "PE1_SH1") (pintype "power_in"))
      (node (ref "X3") (pin "SH2") (pinfunction "PE2_SH2") (pintype "power_in"))
      (node (ref "X3") (pin "SH3") (pinfunction "PE3_SH3") (pintype "power_in"))
      (node (ref "X4") (pin "8") (pinfunction "F_8") (pintype "passive"))
      (node (ref "X4") (pin "G1") (pinfunction "G1_G1") (pintype "passive"))
      (node (ref "X5") (pin "8") (pinfunction "F_8") (pintype "passive"))
      (node (ref "X5") (pin "G1") (pinfunction "G1_G1") (pintype "passive"))
      (node (ref "X7") (pin "3") (pinfunction "3_3") (pintype "power_in"))
      (node (ref "X8") (pin "1") (pinfunction "1_1") (pintype "passive"))
    )
    (net (code "92") (name "Net-(C1-Pad2)") (class "Default")
      (node (ref "C1") (pin "2") (pinfunction "2_2") (pintype "passive"))
      (node (ref "R23") (pin "2") (pinfunction "2_2") (pintype "passive"))
      (node (ref "R48") (pin "1") (pinfunction "1_1") (pintype "passive"))
    )
    (net (code "93") (name "Net-(C2-Pad1)") (class "Default")
      (node (ref "C2") (pin "1") (pinfunction "1_1") (pintype "passive"))
      (node (ref "R17") (pin "2") (pinfunction "2_2") (pintype "passive"))
      (node (ref "X8") (pin "2") (pinfunction "2_2") (pintype "passive"))
      (node (ref "X8") (pin "3") (pinfunction "3_3") (pintype "passive"))
      (node (ref "X8") (pin "4") (pinfunction "4_4") (pintype "passive"))
      (node (ref "X8") (pin "5") (pinfunction "5_5") (pintype "passive"))
    )
    (net (code "94") (name "Net-(C3-Pad1)") (class "Default")
      (node (ref "C3") (pin "1") (pinfunction "1_1") (pintype "passive"))
      (node (ref "R48") (pin "2") (pinfunction "2_2") (pintype "passive"))
    )
    (net (code "95") (name "Net-(C4-Pad1)") (class "Default")
      (node (ref "C4") (pin "1") (pinfunction "1_1") (pintype "passive"))
      (node (ref "R49") (pin "2") (pinfunction "2_2") (pintype "passive"))
    )
    (net (code "96") (name "Net-(C5-Pad2)") (class "Default")
      (node (ref "C5") (pin "2") (pinfunction "2_2") (pintype "passive"))
      (node (ref "R34") (pin "2") (pinfunction "2_2") (pintype "passive"))
      (node (ref "R49") (pin "1") (pinfunction "1_1") (pintype "passive"))
    )
    (net (code "97") (name "Net-(C38-Pad2)") (class "Default")
      (node (ref "C38") (pin "2") (pinfunction "2_2") (pintype "passive"))
      (node (ref "JP2") (pin "1") (pinfunction "1_1") (pintype "passive"))
      (node (ref "Q1") (pin "2") (pinfunction "2_2") (pintype "passive"))
    )
    (net (code "98") (name "Net-(IC1-CLK)") (class "Default")
      (node (ref "IC1") (pin "3") (pinfunction "CLK_3") (pintype "bidirectional"))
      (node (ref "U1") (pin "P72") (pinfunction "CCLK_P72") (pintype "bidirectional"))
    )
    (net (code "99") (name "Net-(IC1-TDI)") (class "Default")
      (node (ref "IC1") (pin "4") (pinfunction "TDI_4") (pintype "bidirectional"))
      (node (ref "U1") (pin "P109") (pinfunction "TDO_P109") (pintype "bidirectional"))
    )
    (net (code "100") (name "Net-(IC1-{slash}CE)") (class "Default")
      (node (ref "IC1") (pin "10") (pinfunction "/CE_10") (pintype "bidirectional"))
      (node (ref "U1") (pin "P71") (pinfunction "DONE_P71") (pintype "bidirectional"))
    )
    (net (code "101") (name "Net-(IC1-{slash}CF)") (class "Default")
      (node (ref "IC1") (pin "7") (pinfunction "/CF_7") (pintype "bidirectional"))
      (node (ref "U1") (pin "P143") (pinfunction "PROG_B_P143") (pintype "bidirectional"))
    )
    (net (code "102") (name "Net-(IC3-D+)") (class "Default")
      (node (ref "IC3") (pin "29") (pinfunction "D+_29") (pintype "bidirectional"))
      (node (ref "R54") (pin "2") (pinfunction "2_2") (pintype "passive"))
    )
    (net (code "103") (name "Net-(IC3-D-)") (class "Default")
      (node (ref "IC3") (pin "30") (pinfunction "D-_30") (pintype "bidirectional"))
      (node (ref "R53") (pin "2") (pinfunction "2_2") (pintype "passive"))
    )
    (net (code "104") (name "Net-(IC3-UCAP)") (class "Default")
      (node (ref "C41") (pin "1") (pinfunction "1_1") (pintype "passive"))
      (node (ref "IC3") (pin "27") (pinfunction "UCAP_27") (pintype "bidirectional"))
    )
    (net (code "105") (name "Net-(IC3-UGND)") (class "Default")
      (node (ref "IC3") (pin "28") (pinfunction "UGND_28") (pintype "bidirectional"))
      (node (ref "X6") (pin "4") (pinfunction "4_4") (pintype "passive"))
    )
    (net (code "106") (name "Net-(IC3-XTAL1)") (class "Default")
      (node (ref "IC3") (pin "1") (pinfunction "XTAL1_1") (pintype "bidirectional"))
      (node (ref "JP2") (pin "2") (pinfunction "2_2") (pintype "passive"))
    )
    (net (code "107") (name "Net-(IC3-XTAL2{slash}PC0)") (class "Default")
      (node (ref "C37") (pin "2") (pinfunction "2_2") (pintype "passive"))
      (node (ref "IC3") (pin "2") (pinfunction "XTAL2/PC0_2") (pintype "bidirectional"))
      (node (ref "Q1") (pin "1") (pinfunction "1_1") (pintype "passive"))
    )
    (net (code "108") (name "Net-(LED1-PadA)") (class "Default")
      (node (ref "LED1") (pin "A") (pinfunction "A_A") (pintype "passive"))
      (node (ref "R11") (pin "2") (pinfunction "2_2") (pintype "passive"))
    )
    (net (code "109") (name "Net-(Q5-B)") (class "Default")
      (node (ref "Q5") (pin "1") (pinfunction "B_1") (pintype "passive"))
      (node (ref "R8") (pin "2") (pinfunction "2_2") (pintype "passive"))
    )
    (net (code "110") (name "Net-(Q5-E)") (class "Default")
      (node (ref "Q5") (pin "2") (pinfunction "E_2") (pintype "passive"))
      (node (ref "R13") (pin "2") (pinfunction "2_2") (pintype "passive"))
      (node (ref "R14") (pin "2") (pinfunction "2_2") (pintype "passive"))
    )
    (net (code "111") (name "Net-(Q6-B)") (class "Default")
      (node (ref "Q6") (pin "1") (pinfunction "B_1") (pintype "passive"))
      (node (ref "R10") (pin "2") (pinfunction "2_2") (pintype "passive"))
      (node (ref "R9") (pin "2") (pinfunction "2_2") (pintype "passive"))
    )
    (net (code "112") (name "Net-(Q6-E)") (class "Default")
      (node (ref "Q6") (pin "2") (pinfunction "E_2") (pintype "passive"))
      (node (ref "R15") (pin "2") (pinfunction "2_2") (pintype "passive"))
      (node (ref "R16") (pin "2") (pinfunction "2_2") (pintype "passive"))
      (node (ref "R20") (pin "2") (pinfunction "2_2") (pintype "passive"))
    )
    (net (code "113") (name "Net-(Q7-B)") (class "Default")
      (node (ref "Q7") (pin "1") (pinfunction "B_1") (pintype "passive"))
      (node (ref "R29") (pin "2") (pinfunction "2_2") (pintype "passive"))
      (node (ref "R30") (pin "2") (pinfunction "2_2") (pintype "passive"))
    )
    (net (code "114") (name "Net-(Q7-E)") (class "Default")
      (node (ref "Q7") (pin "2") (pinfunction "E_2") (pintype "passive"))
      (node (ref "R31") (pin "2") (pinfunction "2_2") (pintype "passive"))
      (node (ref "R32") (pin "2") (pinfunction "2_2") (pintype "passive"))
      (node (ref "R33") (pin "2") (pinfunction "2_2") (pintype "passive"))
    )
    (net (code "115") (name "Net-(Q8-B)") (class "Default")
      (node (ref "Q8") (pin "1") (pinfunction "B_1") (pintype "passive"))
      (node (ref "R24") (pin "2") (pinfunction "2_2") (pintype "passive"))
      (node (ref "R25") (pin "2") (pinfunction "2_2") (pintype "passive"))
    )
    (net (code "116") (name "Net-(Q8-E)") (class "Default")
      (node (ref "Q8") (pin "2") (pinfunction "E_2") (pintype "passive"))
      (node (ref "R26") (pin "2") (pinfunction "2_2") (pintype "passive"))
      (node (ref "R27") (pin "2") (pinfunction "2_2") (pintype "passive"))
      (node (ref "R28") (pin "2") (pinfunction "2_2") (pintype "passive"))
    )
    (net (code "117") (name "Net-(R18-Pad2)") (class "Default")
      (node (ref "R18") (pin "2") (pinfunction "2_2") (pintype "passive"))
      (node (ref "R22") (pin "2") (pinfunction "2_2") (pintype "passive"))
    )
    (net (code "118") (name "Net-(R53-Pad1)") (class "Default")
      (node (ref "R53") (pin "1") (pinfunction "1_1") (pintype "passive"))
      (node (ref "X6") (pin "2") (pinfunction "2_2") (pintype "passive"))
    )
    (net (code "119") (name "Net-(R54-Pad1)") (class "Default")
      (node (ref "R54") (pin "1") (pinfunction "1_1") (pintype "passive"))
      (node (ref "X6") (pin "3") (pinfunction "3_3") (pintype "passive"))
    )
    (net (code "120") (name "Net-(T2-B)") (class "Default")
      (node (ref "C2") (pin "2") (pinfunction "2_2") (pintype "passive"))
      (node (ref "R18") (pin "1") (pinfunction "1_1") (pintype "passive"))
      (node (ref "R19") (pin "2") (pinfunction "2_2") (pintype "passive"))
      (node (ref "T2") (pin "1") (pinfunction "B_1") (pintype "passive"))
    )
    (net (code "121") (name "Net-(U$6-A0)") (class "Default")
      (node (ref "U$6") (pin "P20") (pinfunction "A0_P20") (pintype "bidirectional"))
      (node (ref "U1") (pin "P24") (pinfunction "IO_L24N_6VREF_6_P24") (pintype "bidirectional"))
    )
    (net (code "122") (name "Net-(U$6-A1)") (class "Default")
      (node (ref "U$6") (pin "P19") (pinfunction "A1_P19") (pintype "bidirectional"))
      (node (ref "U1") (pin "P23") (pinfunction "IO_L24P_6_P23") (pintype "bidirectional"))
    )
    (net (code "123") (name "Net-(U$6-A2)") (class "Default")
      (node (ref "U$6") (pin "P18") (pinfunction "A2_P18") (pintype "bidirectional"))
      (node (ref "U1") (pin "P21") (pinfunction "IO_L40N_6_P21") (pintype "bidirectional"))
    )
    (net (code "124") (name "Net-(U$6-A3)") (class "Default")
      (node (ref "U$6") (pin "P17") (pinfunction "A3_P17") (pintype "bidirectional"))
      (node (ref "U1") (pin "P20") (pinfunction "IO_L40P_6VREF_6_P20") (pintype "bidirectional"))
    )
    (net (code "125") (name "Net-(U$6-A4)") (class "Default")
      (node (ref "U$6") (pin "P16") (pinfunction "A4_P16") (pintype "bidirectional"))
      (node (ref "U1") (pin "P18") (pinfunction "IO_L40N_7VREF_7_P18") (pintype "bidirectional"))
    )
    (net (code "126") (name "Net-(U$6-A5)") (class "Default")
      (node (ref "U$6") (pin "P15") (pinfunction "A5_P15") (pintype "bidirectional"))
      (node (ref "U1") (pin "P17") (pinfunction "IO_L40P_7_P17") (pintype "bidirectional"))
    )
    (net (code "127") (name "Net-(U$6-A6)") (class "Default")
      (node (ref "U$6") (pin "P14") (pinfunction "A6_P14") (pintype "bidirectional"))
      (node (ref "U1") (pin "P15") (pinfunction "IO_L24N_7_P15") (pintype "bidirectional"))
    )
    (net (code "128") (name "Net-(U$6-A7)") (class "Default")
      (node (ref "U$6") (pin "P13") (pinfunction "A7_P13") (pintype "bidirectional"))
      (node (ref "U1") (pin "P14") (pinfunction "IO_L24P_7_P14") (pintype "bidirectional"))
    )
    (net (code "129") (name "Net-(U$6-A8)") (class "Default")
      (node (ref "U$6") (pin "P3") (pinfunction "A8_P3") (pintype "bidirectional"))
      (node (ref "U1") (pin "P4") (pinfunction "IOVREF_7_P4") (pintype "bidirectional"))
    )
    (net (code "130") (name "Net-(U$6-A9)") (class "Default")
      (node (ref "U$6") (pin "P2") (pinfunction "A9_P2") (pintype "bidirectional"))
      (node (ref "U1") (pin "P2") (pinfunction "IO_L01N_7VRP_7_P2") (pintype "bidirectional"))
    )
    (net (code "131") (name "Net-(U$6-A10)") (class "Default")
      (node (ref "U$6") (pin "P31") (pinfunction "A10_P31") (pintype "bidirectional"))
      (node (ref "U1") (pin "P35") (pinfunction "IO_L01P_6VRN_6_P35") (pintype "bidirectional"))
    )
    (net (code "132") (name "Net-(U$6-A11)") (class "Default")
      (node (ref "U$6") (pin "P1") (pinfunction "A11_P1") (pintype "bidirectional"))
      (node (ref "U1") (pin "P1") (pinfunction "IO_L01P_7VRN_7_P1") (pintype "bidirectional"))
    )
    (net (code "133") (name "Net-(U$6-A12)") (class "Default")
      (node (ref "U$6") (pin "P12") (pinfunction "A12_P12") (pintype "bidirectional"))
      (node (ref "U1") (pin "P13") (pinfunction "IO_L23N_7_P13") (pintype "bidirectional"))
    )
    (net (code "134") (name "Net-(U$6-A13)") (class "Default")
      (node (ref "U$6") (pin "P4") (pinfunction "A13_P4") (pintype "bidirectional"))
      (node (ref "U1") (pin "P5") (pinfunction "IO_L20P_7_P5") (pintype "bidirectional"))
    )
    (net (code "135") (name "Net-(U$6-A14)") (class "Default")
      (node (ref "U$6") (pin "P11") (pinfunction "A14_P11") (pintype "bidirectional"))
      (node (ref "U1") (pin "P12") (pinfunction "IO_L23P_7_P12") (pintype "bidirectional"))
    )
    (net (code "136") (name "Net-(U$6-A15)") (class "Default")
      (node (ref "U$6") (pin "P7") (pinfunction "A15_P7") (pintype "bidirectional"))
      (node (ref "U1") (pin "P8") (pinfunction "IO_L21N_7_P8") (pintype "bidirectional"))
    )
    (net (code "137") (name "Net-(U$6-A16)") (class "Default")
      (node (ref "U$6") (pin "P10") (pinfunction "A16_P10") (pintype "bidirectional"))
      (node (ref "U1") (pin "P11") (pinfunction "IO_L22N_7_P11") (pintype "bidirectional"))
    )
    (net (code "138") (name "Net-(U$6-A17)") (class "Default")
      (node (ref "U$6") (pin "P6") (pinfunction "A17_P6") (pintype "bidirectional"))
      (node (ref "U1") (pin "P7") (pinfunction "IO_L21P_7_P7") (pintype "bidirectional"))
    )
    (net (code "139") (name "Net-(U$6-A18)") (class "Default")
      (node (ref "U$6") (pin "P9") (pinfunction "A18_P9") (pintype "bidirectional"))
      (node (ref "U1") (pin "P10") (pinfunction "IO_L22P_7_P10") (pintype "bidirectional"))
    )
    (net (code "140") (name "Net-(U$6-DQ0)") (class "Default")
      (node (ref "U$6") (pin "P21") (pinfunction "DQ0_P21") (pintype "bidirectional"))
      (node (ref "U1") (pin "P25") (pinfunction "IO_L23P_6_P25") (pintype "bidirectional"))
    )
    (net (code "141") (name "Net-(U$6-DQ1)") (class "Default")
      (node (ref "U$6") (pin "P22") (pinfunction "DQ1_P22") (pintype "bidirectional"))
      (node (ref "U1") (pin "P26") (pinfunction "IO_L23N_6_P26") (pintype "bidirectional"))
    )
    (net (code "142") (name "Net-(U$6-DQ2)") (class "Default")
      (node (ref "U$6") (pin "P23") (pinfunction "DQ2_P23") (pintype "bidirectional"))
      (node (ref "U1") (pin "P27") (pinfunction "IO_L22P_6_P27") (pintype "bidirectional"))
    )
    (net (code "143") (name "Net-(U$6-DQ3)") (class "Default")
      (node (ref "U$6") (pin "P25") (pinfunction "DQ3_P25") (pintype "bidirectional"))
      (node (ref "U1") (pin "P28") (pinfunction "IO_L22N_6_P28") (pintype "bidirectional"))
    )
    (net (code "144") (name "Net-(U$6-DQ4)") (class "Default")
      (node (ref "U$6") (pin "P26") (pinfunction "DQ4_P26") (pintype "bidirectional"))
      (node (ref "U1") (pin "P30") (pinfunction "IO_L21P_6_P30") (pintype "bidirectional"))
    )
    (net (code "145") (name "Net-(U$6-DQ5)") (class "Default")
      (node (ref "U$6") (pin "P27") (pinfunction "DQ5_P27") (pintype "bidirectional"))
      (node (ref "U1") (pin "P31") (pinfunction "IO_L21N_6_P31") (pintype "bidirectional"))
    )
    (net (code "146") (name "Net-(U$6-DQ6)") (class "Default")
      (node (ref "U$6") (pin "P28") (pinfunction "DQ6_P28") (pintype "bidirectional"))
      (node (ref "U1") (pin "P32") (pinfunction "IO_L20P_6_P32") (pintype "bidirectional"))
    )
    (net (code "147") (name "Net-(U$6-DQ7)") (class "Default")
      (node (ref "U$6") (pin "P29") (pinfunction "DQ7_P29") (pintype "bidirectional"))
      (node (ref "U1") (pin "P33") (pinfunction "IO_L20N_6_P33") (pintype "bidirectional"))
    )
    (net (code "148") (name "Net-(U$6-OE)") (class "Default")
      (node (ref "U$6") (pin "P32") (pinfunction "OE_P32") (pintype "bidirectional"))
      (node (ref "U1") (pin "P36") (pinfunction "IO_L01N_6VRP_6_P36") (pintype "bidirectional"))
    )
    (net (code "149") (name "Net-(U$6-WE)") (class "Default")
      (node (ref "U$6") (pin "P5") (pinfunction "WE_P5") (pintype "bidirectional"))
      (node (ref "U1") (pin "P6") (pinfunction "IO_L20N_7_P6") (pintype "bidirectional"))
    )
    (net (code "150") (name "Net-(U1A-IO_L27N_0)") (class "Default")
      (node (ref "SV3") (pin "3") (pinfunction "3_3") (pintype "passive"))
      (node (ref "U1") (pin "P137") (pinfunction "IO_L27N_0_P137") (pintype "bidirectional"))
    )
    (net (code "151") (name "Net-(U1A-IO_L27P_0)") (class "Default")
      (node (ref "SV3") (pin "4") (pinfunction "4_4") (pintype "passive"))
      (node (ref "U1") (pin "P135") (pinfunction "IO_L27P_0_P135") (pintype "bidirectional"))
    )
    (net (code "152") (name "Net-(U1A-IO_L30N_0)") (class "Default")
      (node (ref "SV3") (pin "5") (pinfunction "5_5") (pintype "passive"))
      (node (ref "U1") (pin "P132") (pinfunction "IO_L30N_0_P132") (pintype "bidirectional"))
    )
    (net (code "153") (name "Net-(U1A-IO_L31N_0)") (class "Default")
      (node (ref "SV3") (pin "6") (pinfunction "6_6") (pintype "passive"))
      (node (ref "U1") (pin "P130") (pinfunction "IO_L31N_0_P130") (pintype "bidirectional"))
    )
    (net (code "154") (name "Net-(U1A-IO_L31P_0VREF_0)") (class "Default")
      (node (ref "SV3") (pin "7") (pinfunction "7_7") (pintype "passive"))
      (node (ref "U1") (pin "P129") (pinfunction "IO_L31P_0VREF_0_P129") (pintype "bidirectional"))
    )
    (net (code "155") (name "Net-(U1A-IO_L32N_0GCLK7)") (class "Default")
      (node (ref "SV3") (pin "9") (pinfunction "9_9") (pintype "passive"))
      (node (ref "U1") (pin "P128") (pinfunction "IO_L32N_0GCLK7_P128") (pintype "bidirectional"))
    )
    (net (code "156") (name "Net-(U1A-IO_L32P_0GCLK6)") (class "Default")
      (node (ref "SV3") (pin "8") (pinfunction "8_8") (pintype "passive"))
      (node (ref "U1") (pin "P127") (pinfunction "IO_L32P_0GCLK6_P127") (pintype "bidirectional"))
    )
    (net (code "157") (name "Net-(U1C-IO_L31N_1VREF_1)") (class "Default")
      (node (ref "SV3") (pin "10") (pinfunction "10_10") (pintype "passive"))
      (node (ref "U1") (pin "P123") (pinfunction "IO_L31N_1VREF_1_P123") (pintype "bidirectional"))
    )
    (net (code "158") (name "Net-(U1N-TCK)") (class "Default")
      (node (ref "R2") (pin "1") (pinfunction "1_1") (pintype "passive"))
      (node (ref "U1") (pin "P110") (pinfunction "TCK_P110") (pintype "bidirectional"))
    )
    (net (code "159") (name "Net-(U1N-TDI)") (class "Default")
      (node (ref "R1") (pin "1") (pinfunction "1_1") (pintype "passive"))
      (node (ref "U1") (pin "P144") (pinfunction "TDI_P144") (pintype "bidirectional"))
    )
    (net (code "160") (name "Net-(U1N-TMS)") (class "Default")
      (node (ref "R3") (pin "1") (pinfunction "1_1") (pintype "passive"))
      (node (ref "U1") (pin "P111") (pinfunction "TMS_P111") (pintype "bidirectional"))
    )
    (net (code "161") (name "unconnected-(IC1-NC.1-Pad2)") (class "Default")
      (node (ref "IC1") (pin "2") (pinfunction "NC.1_2") (pintype "bidirectional"))
    )
    (net (code "162") (name "unconnected-(IC1-NC.2-Pad9)") (class "Default")
      (node (ref "IC1") (pin "9") (pinfunction "NC.2_9") (pintype "bidirectional"))
    )
    (net (code "163") (name "unconnected-(IC1-NC.3-Pad12)") (class "Default")
      (node (ref "IC1") (pin "12") (pinfunction "NC.3_12") (pintype "bidirectional"))
    )
    (net (code "164") (name "unconnected-(IC1-NC.4-Pad14)") (class "Default")
      (node (ref "IC1") (pin "14") (pinfunction "NC.4_14") (pintype "bidirectional"))
    )
    (net (code "165") (name "unconnected-(IC1-NC.5-Pad15)") (class "Default")
      (node (ref "IC1") (pin "15") (pinfunction "NC.5_15") (pintype "bidirectional"))
    )
    (net (code "166") (name "unconnected-(IC1-NC.6-Pad16)") (class "Default")
      (node (ref "IC1") (pin "16") (pinfunction "NC.6_16") (pintype "bidirectional"))
    )
    (net (code "167") (name "unconnected-(IC1-{slash}CEO-Pad13)") (class "Default")
      (node (ref "IC1") (pin "13") (pinfunction "/CEO_13") (pintype "bidirectional"))
    )
    (net (code "168") (name "unconnected-(REG1.2-VOUT2-Pad2)") (class "Default")
      (node (ref "REG1.2") (pin "2") (pinfunction "VOUT2_2") (pintype "bidirectional"))
    )
    (net (code "169") (name "unconnected-(REG2.5-VOUT2-Pad2)") (class "Default")
      (node (ref "REG2.5") (pin "2") (pinfunction "VOUT2_2") (pintype "bidirectional"))
    )
    (net (code "170") (name "unconnected-(U$2-TRI-PadENA)") (class "Default")
      (node (ref "U$2") (pin "ENA") (pinfunction "TRI_ENA") (pintype "input"))
    )
    (net (code "171") (name "unconnected-(U$3-CARD_DETECT-PadCD)") (class "Default")
      (node (ref "U$3") (pin "CD") (pinfunction "CARD_DETECT_CD") (pintype "passive"))
    )
    (net (code "172") (name "unconnected-(U$3-DAT1-Pad8)") (class "Default")
      (node (ref "U$3") (pin "8") (pinfunction "DAT1_8") (pintype "bidirectional"))
    )
    (net (code "173") (name "unconnected-(U$3-DAT2-Pad9)") (class "Default")
      (node (ref "U$3") (pin "9") (pinfunction "DAT2_9") (pintype "bidirectional"))
    )
    (net (code "174") (name "unconnected-(U$3-WRITE_PROTECT-PadWP)") (class "Default")
      (node (ref "U$3") (pin "WP") (pinfunction "WRITE_PROTECT_WP") (pintype "passive"))
    )
    (net (code "175") (name "unconnected-(U$4-VOUT2-Pad2)") (class "Default")
      (node (ref "U$4") (pin "2") (pinfunction "VOUT2_2") (pintype "bidirectional"))
    )
    (net (code "176") (name "unconnected-(U1N-HSWAP_EN-PadP142)") (class "Default")
      (node (ref "U1") (pin "P142") (pinfunction "HSWAP_EN_P142") (pintype "bidirectional"))
    )
    (net (code "177") (name "unconnected-(X1-Pad10)") (class "Default")
      (node (ref "X1") (pin "10") (pinfunction "10_10") (pintype "passive"))
    )
    (net (code "178") (name "unconnected-(X1-Pad12)") (class "Default")
      (node (ref "X1") (pin "12") (pinfunction "12_12") (pintype "passive"))
    )
    (net (code "179") (name "unconnected-(X3-Pad2)") (class "Default")
      (node (ref "X3") (pin "2") (pinfunction "2_2") (pintype "passive"))
    )
    (net (code "180") (name "unconnected-(X3-Pad8)") (class "Default")
      (node (ref "X3") (pin "8") (pinfunction "8_8") (pintype "passive"))
    )
    (net (code "181") (name "unconnected-(X4-PadG2)") (class "Default")
      (node (ref "X4") (pin "G2") (pinfunction "G2_G2") (pintype "passive"))
    )
    (net (code "182") (name "unconnected-(X5-PadG2)") (class "Default")
      (node (ref "X5") (pin "G2") (pinfunction "G2_G2") (pintype "passive"))
    )
    (net (code "183") (name "unconnected-(X6-Pad1)") (class "Default")
      (node (ref "X6") (pin "1") (pinfunction "1_1") (pintype "passive"))
    )
  )
)
